# io-board-b-8.net
KiCad netlist of a schematic drawn in EAGLE
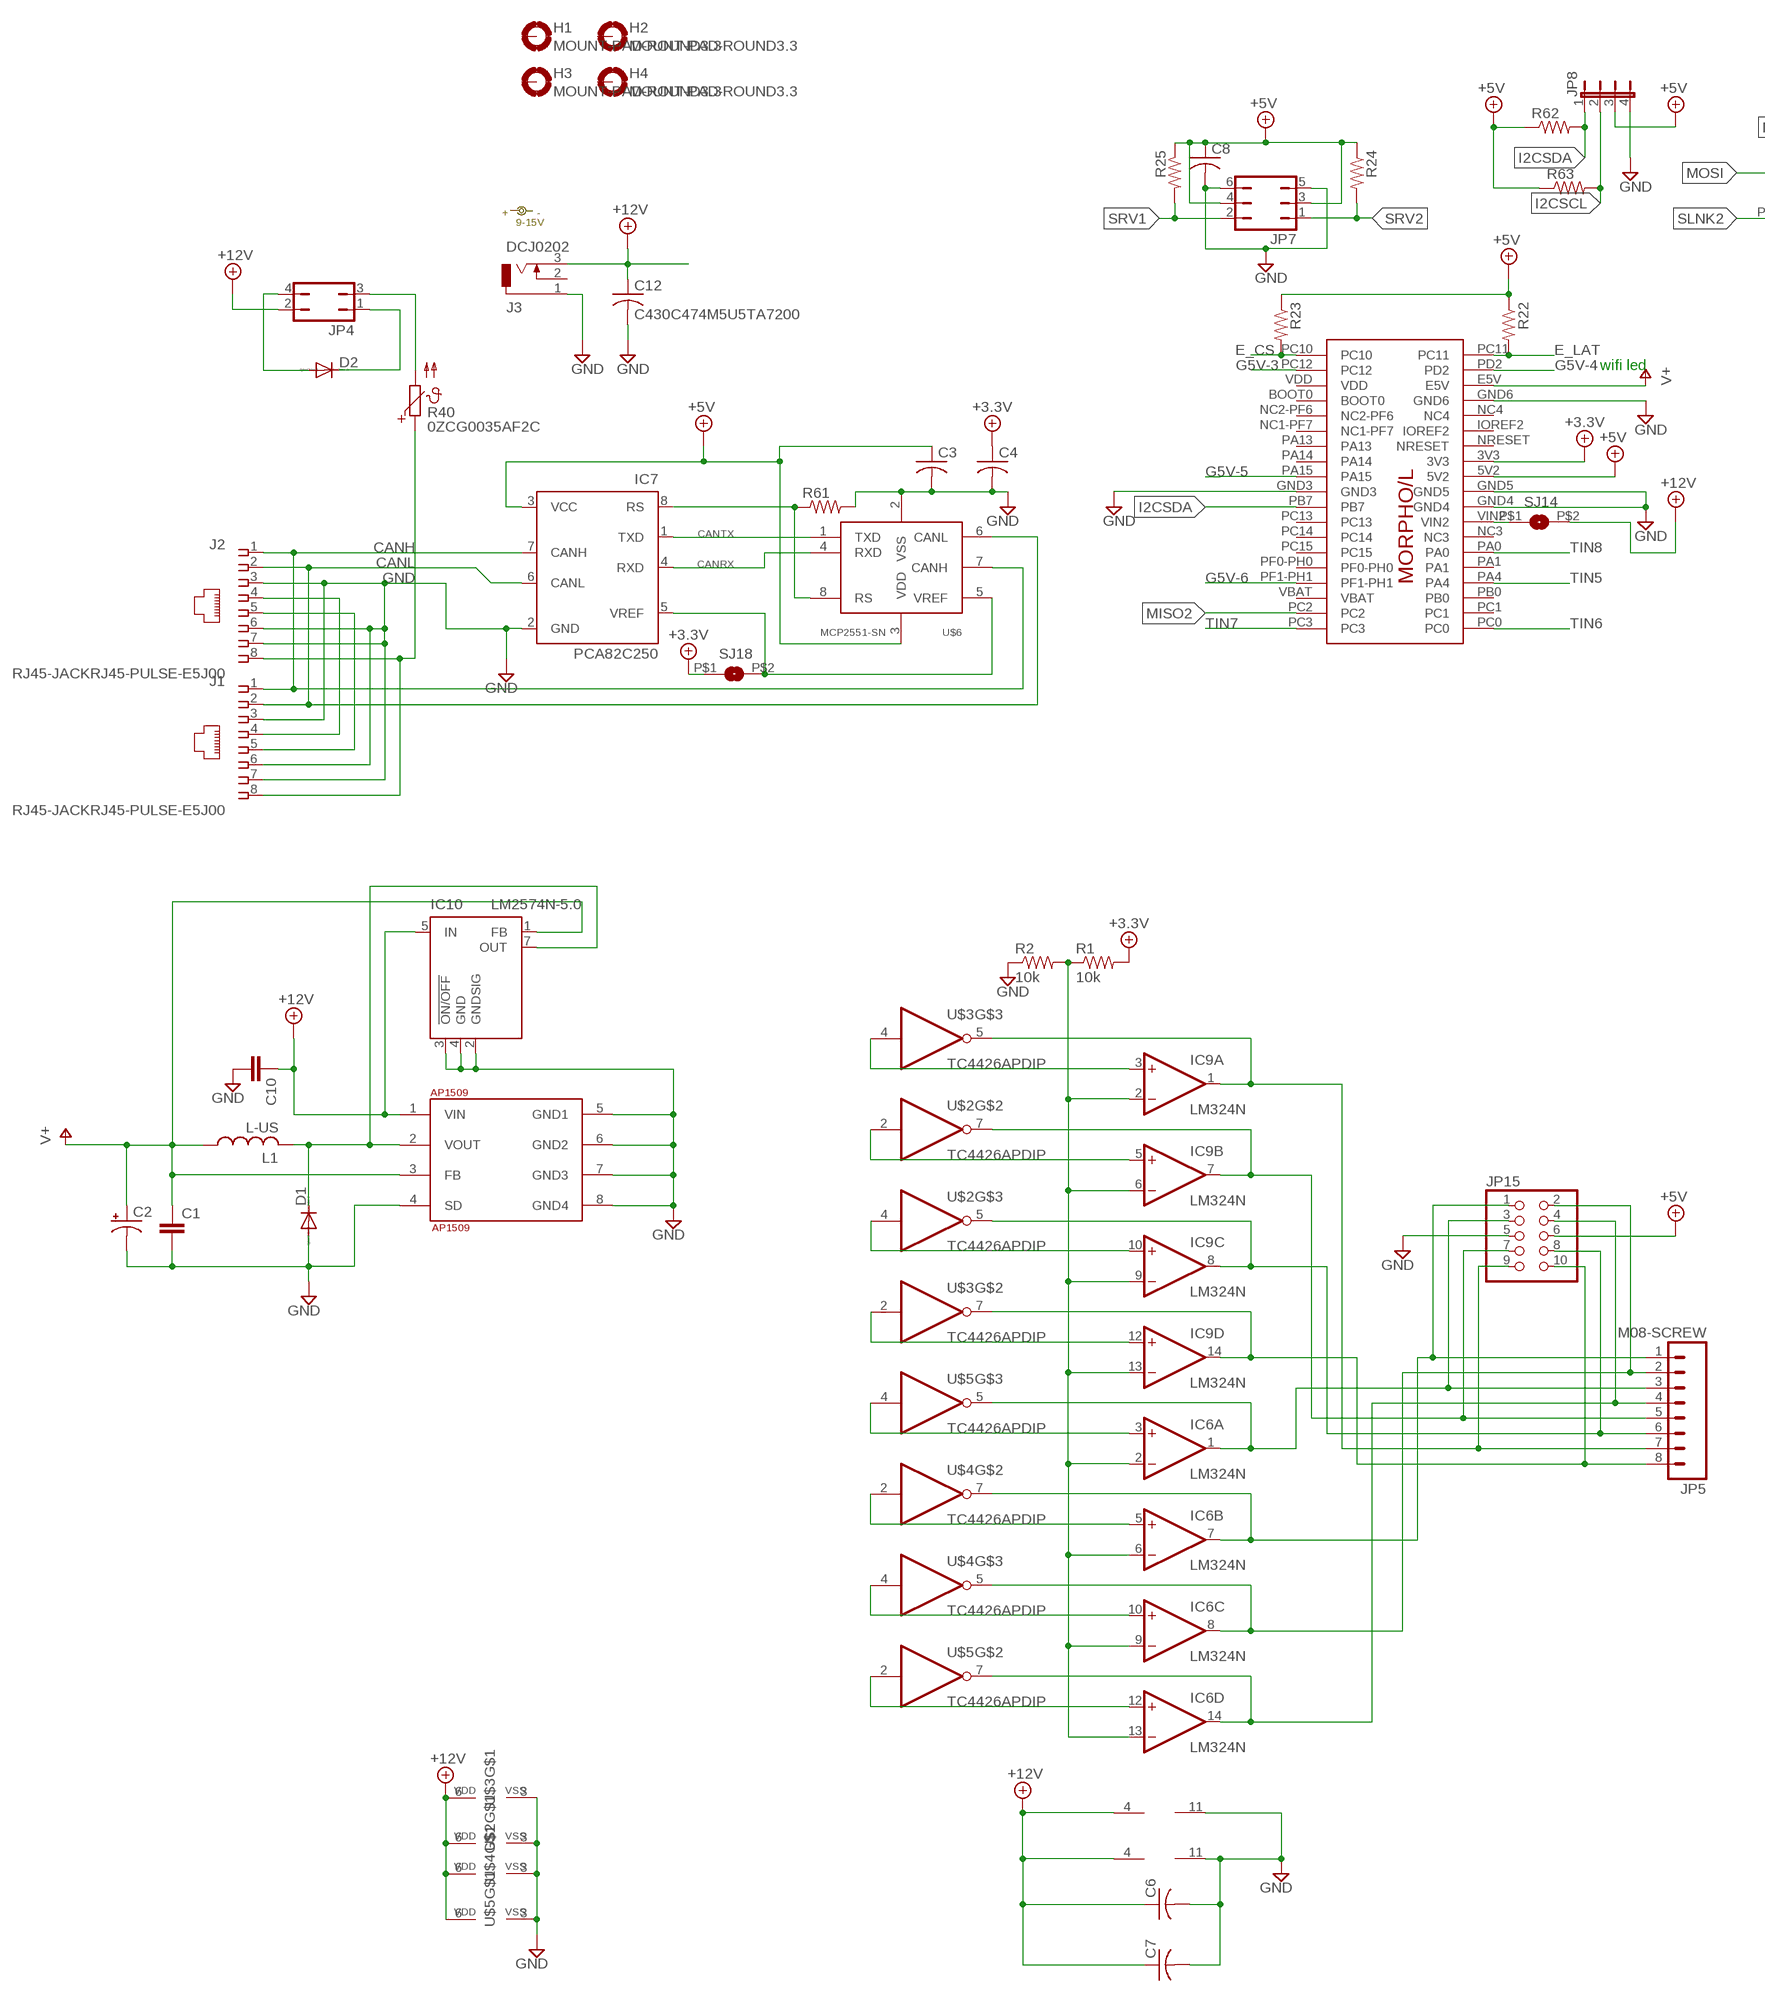
[diagram p0: schematic, sheet 1, part 1 of 2]
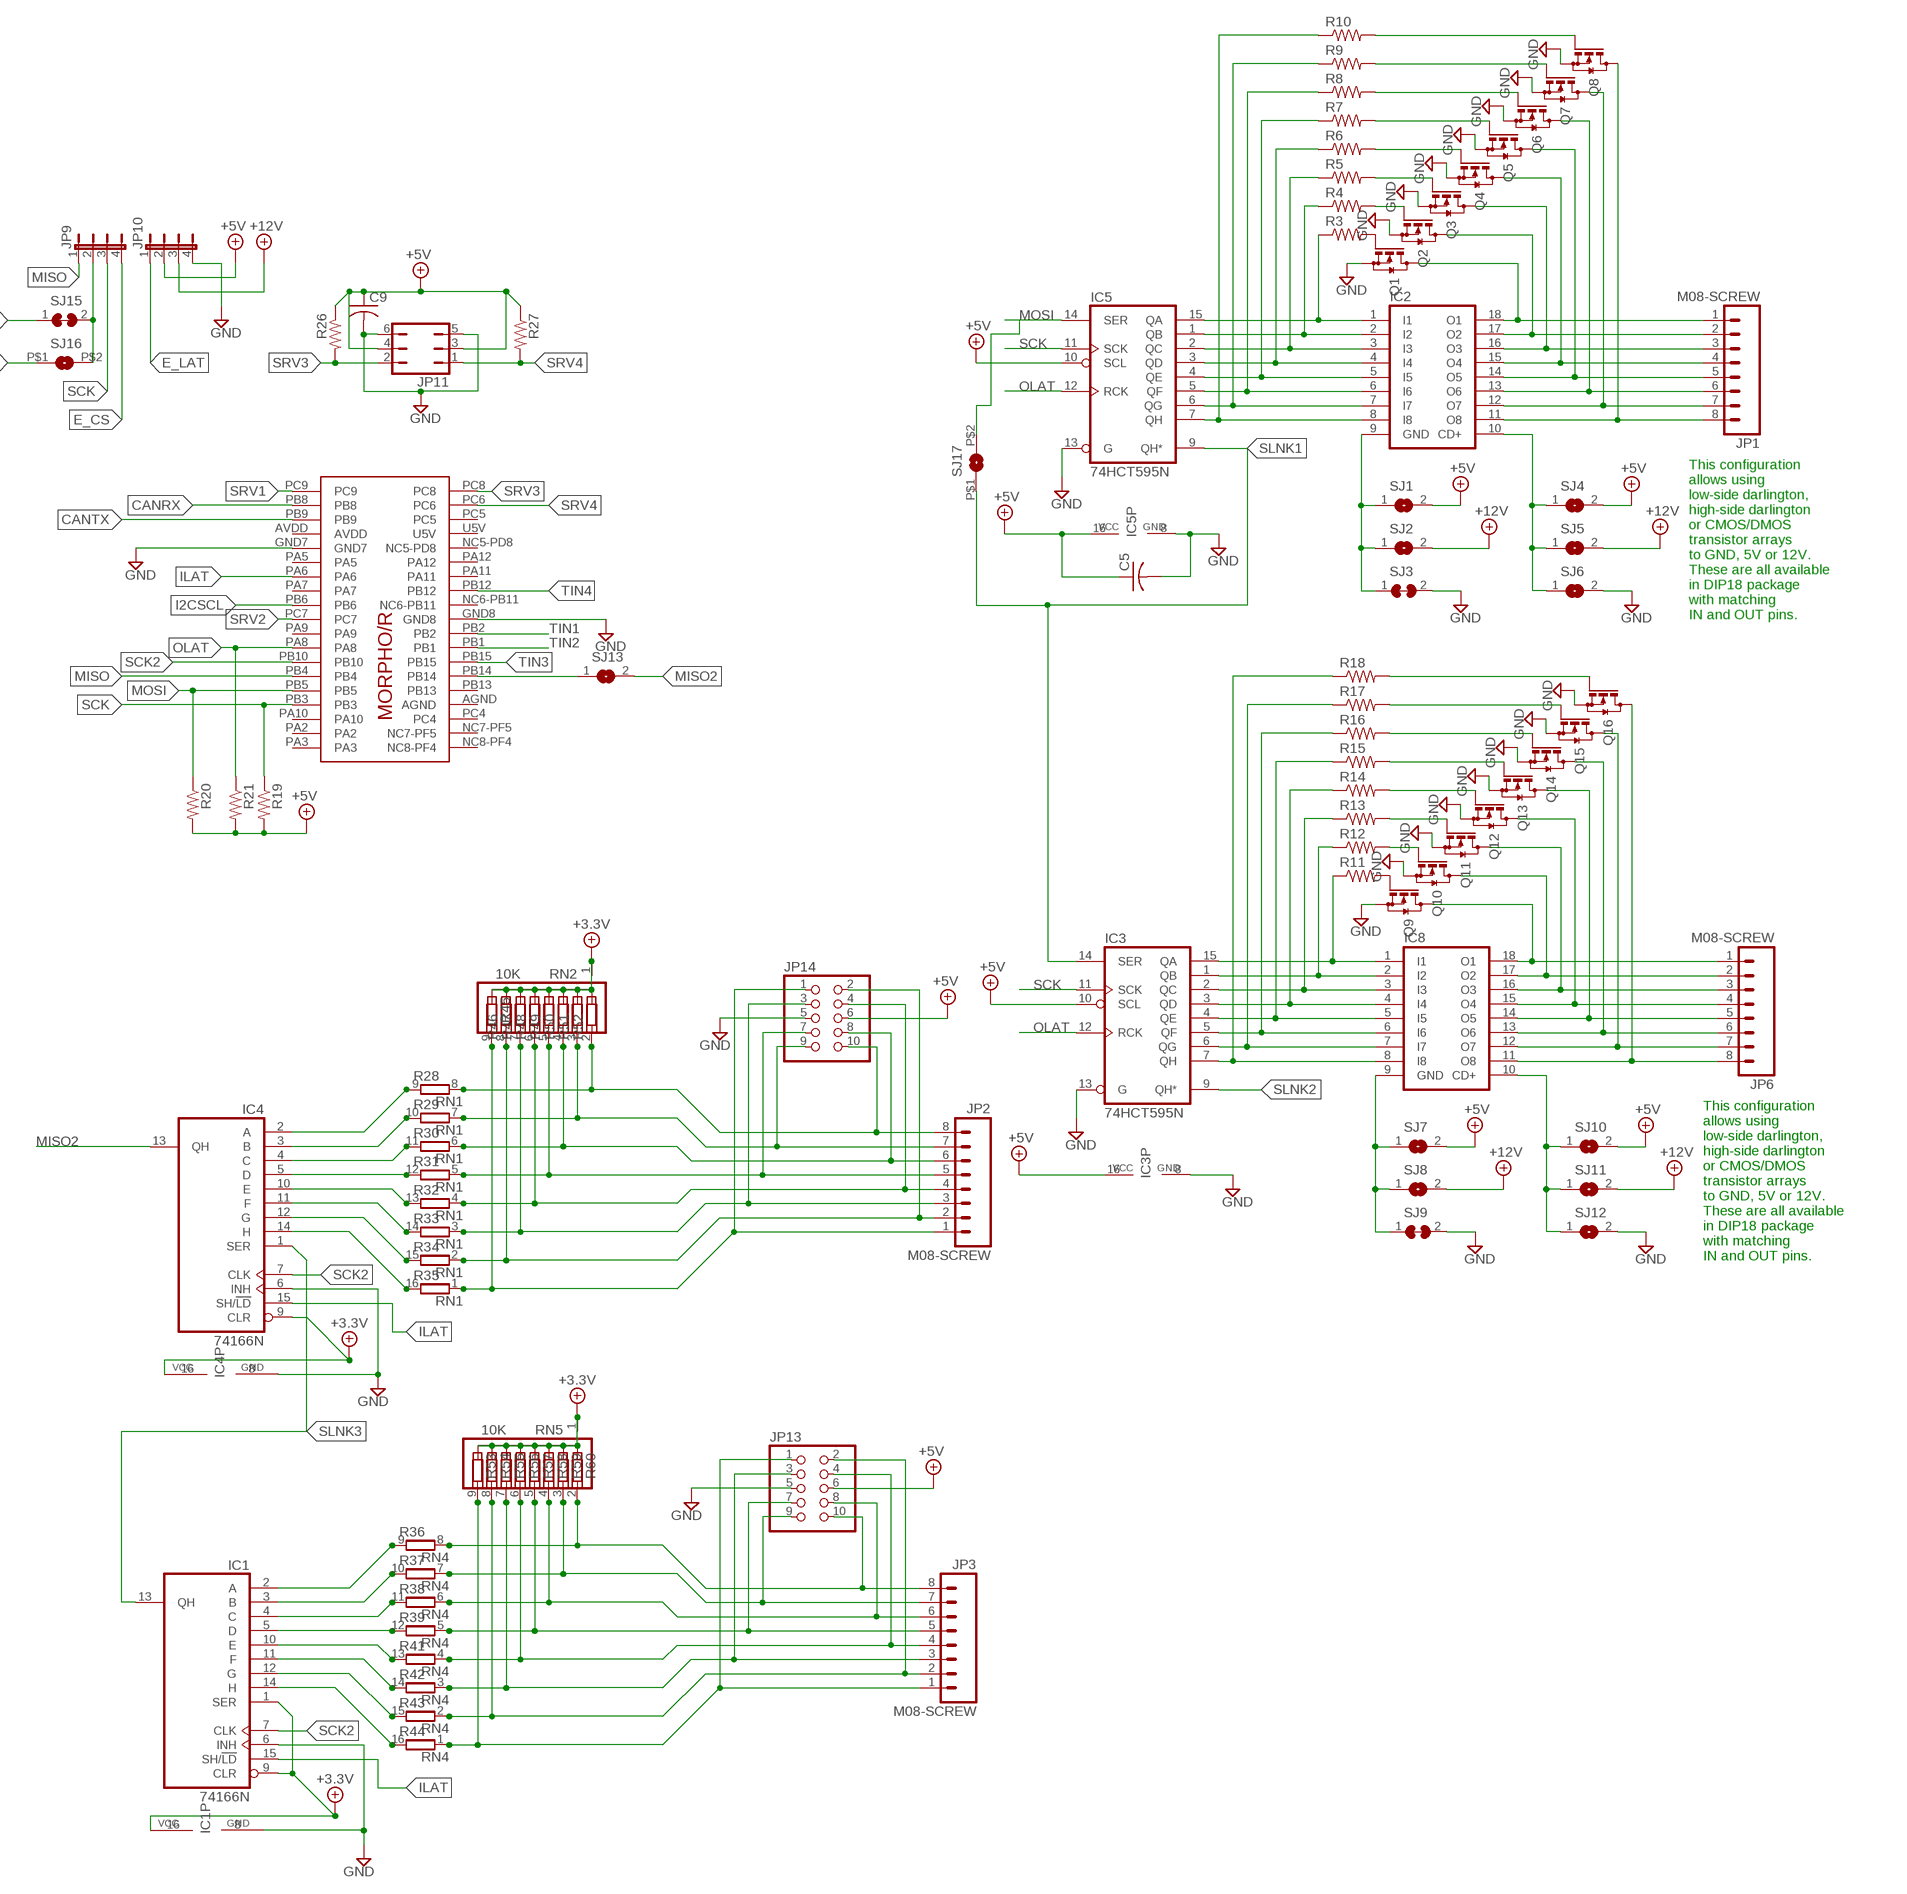
[diagram p1: schematic, sheet 1, part 2 of 2]

(export (version "E")
  (design (tool "Eeschema 10.0.6"))
  (components
    (comp (ref "+12V")
      (value "9-15V")
      (footprint "eagle-import:POWER_USAGE")
      (libsource (lib "eagle-import") (part "DOC-POWER_LABEL"))
    )
    (comp (ref "AP1509")
      (value "AP1509")
      (footprint "eagle-import:SO-08")
      (libsource (lib "eagle-import") (part "AP1509"))
    )
    (comp (ref "C1")
      (value "C-EUC1206")
      (footprint "eagle-import:C1206")
      (libsource (lib "eagle-import") (part "C-EUC1206"))
    )
    (comp (ref "C2")
      (value "CPOL-USE2.5-5")
      (footprint "eagle-import:E2,5-5")
      (libsource (lib "eagle-import") (part "CPOL-USE2.5-5"))
    )
    (comp (ref "C3")
      (value "C-USC0805")
      (footprint "eagle-import:C0805")
      (libsource (lib "eagle-import") (part "C-USC0805"))
    )
    (comp (ref "C4")
      (value "C-USC0805")
      (footprint "eagle-import:C0805")
      (libsource (lib "eagle-import") (part "C-USC0805"))
    )
    (comp (ref "C5")
      (value "C-USC0805")
      (footprint "eagle-import:C0805")
      (libsource (lib "eagle-import") (part "C-USC0805"))
    )
    (comp (ref "C6")
      (value "C-USC1206")
      (footprint "eagle-import:C1206")
      (libsource (lib "eagle-import") (part "C-USC1206"))
    )
    (comp (ref "C7")
      (value "C-USC1206")
      (footprint "eagle-import:C1206")
      (libsource (lib "eagle-import") (part "C-USC1206"))
    )
    (comp (ref "C8")
      (value "C-USC1206")
      (footprint "eagle-import:C1206")
      (libsource (lib "eagle-import") (part "C-USC1206"))
    )
    (comp (ref "C9")
      (value "C-USC1206")
      (footprint "eagle-import:C1206")
      (libsource (lib "eagle-import") (part "C-USC1206"))
    )
    (comp (ref "C10")
      (value "C-EUC1206")
      (footprint "eagle-import:C1206")
      (libsource (lib "eagle-import") (part "C-EUC1206"))
    )
    (comp (ref "C12")
      (value "C430C474M5U5TA7200")
      (footprint "eagle-import:C075-032X103")
      (libsource (lib "eagle-import") (part "C-US075-032X103"))
    )
    (comp (ref "D1")
      (value "DIODE-DO41-7.6")
      (footprint "eagle-import:DO41-7.6")
      (libsource (lib "eagle-import") (part "DIODE-DO41-7.6"))
    )
    (comp (ref "D2")
      (value "DIODE-DO41-7.6")
      (footprint "eagle-import:DO41-7.6")
      (libsource (lib "eagle-import") (part "DIODE-DO41-7.6"))
    )
    (comp (ref "H1")
      (value "MOUNT-PAD-ROUND3.3")
      (footprint "eagle-import:3,3-PAD")
      (libsource (lib "eagle-import") (part "MOUNT-PAD-ROUND3.3"))
    )
    (comp (ref "H2")
      (value "MOUNT-PAD-ROUND3.3")
      (footprint "eagle-import:3,3-PAD")
      (libsource (lib "eagle-import") (part "MOUNT-PAD-ROUND3.3"))
    )
    (comp (ref "H3")
      (value "MOUNT-PAD-ROUND3.3")
      (footprint "eagle-import:3,3-PAD")
      (libsource (lib "eagle-import") (part "MOUNT-PAD-ROUND3.3"))
    )
    (comp (ref "H4")
      (value "MOUNT-PAD-ROUND3.3")
      (footprint "eagle-import:3,3-PAD")
      (libsource (lib "eagle-import") (part "MOUNT-PAD-ROUND3.3"))
    )
    (comp (ref "IC1")
      (value "74166N")
      (footprint "eagle-import:DIL16")
      (libsource (lib "eagle-import") (part "74166N"))
    )
    (comp (ref "IC2")
      (value "ULN2803A")
      (footprint "eagle-import:DIL18-THIN")
      (libsource (lib "eagle-import") (part "ULN2803A"))
    )
    (comp (ref "IC3")
      (value "74HCT595N")
      (footprint "eagle-import:DIL16")
      (libsource (lib "eagle-import") (part "74595NHCT"))
    )
    (comp (ref "IC4")
      (value "74166N")
      (footprint "eagle-import:DIL16")
      (libsource (lib "eagle-import") (part "74166N"))
    )
    (comp (ref "IC5")
      (value "74HCT595N")
      (footprint "eagle-import:DIL16")
      (libsource (lib "eagle-import") (part "74595NHCT"))
    )
    (comp (ref "IC6")
      (value "LM324N")
      (footprint "eagle-import:DIL14")
      (libsource (lib "eagle-import") (part "LM324N"))
    )
    (comp (ref "IC7")
      (value "PCA82C250")
      (footprint "eagle-import:DIL08")
      (libsource (lib "eagle-import") (part "PCA82C250"))
    )
    (comp (ref "IC8")
      (value "ULN2803A")
      (footprint "eagle-import:DIL18-THIN")
      (libsource (lib "eagle-import") (part "ULN2803A"))
    )
    (comp (ref "IC9")
      (value "LM324N")
      (footprint "eagle-import:DIL14")
      (libsource (lib "eagle-import") (part "LM324N"))
    )
    (comp (ref "IC10")
      (value "LM2574N-5.0")
      (footprint "eagle-import:DIL08")
      (libsource (lib "eagle-import") (part "LM2574?-N5.0"))
    )
    (comp (ref "J1")
      (value "RJ45-JACKRJ45-PULSE-E5J00")
      (footprint "eagle-import:RJ45-PULSE-E5J88")
      (libsource (lib "eagle-import") (part "RJ45-JACKRJ45-PULSE-E5J00"))
    )
    (comp (ref "J2")
      (value "RJ45-JACKRJ45-PULSE-E5J00")
      (footprint "eagle-import:RJ45-PULSE-E5J88")
      (libsource (lib "eagle-import") (part "RJ45-JACKRJ45-PULSE-E5J00"))
    )
    (comp (ref "J3")
      (value "DCJ0202")
      (footprint "eagle-import:DCJ0202")
      (libsource (lib "eagle-import") (part "DCJ0202"))
    )
    (comp (ref "JP1")
      (value "M08-SCREW")
      (footprint "eagle-import:1X08_TERMINAL")
      (libsource (lib "eagle-import") (part "M08-SCREW"))
    )
    (comp (ref "JP2")
      (value "M08-SCREW")
      (footprint "eagle-import:1X08_TERMINAL")
      (libsource (lib "eagle-import") (part "M08-SCREW"))
    )
    (comp (ref "JP3")
      (value "M08-SCREW")
      (footprint "eagle-import:1X08_TERMINAL")
      (libsource (lib "eagle-import") (part "M08-SCREW"))
    )
    (comp (ref "JP4")
      (value "JP2Q")
      (footprint "eagle-import:JP2Q")
      (libsource (lib "eagle-import") (part "JP2Q"))
    )
    (comp (ref "JP5")
      (value "M08-SCREW")
      (footprint "eagle-import:1X08_TERMINAL")
      (libsource (lib "eagle-import") (part "M08-SCREW"))
    )
    (comp (ref "JP6")
      (value "M08-SCREW")
      (footprint "eagle-import:1X08_TERMINAL")
      (libsource (lib "eagle-import") (part "M08-SCREW"))
    )
    (comp (ref "JP7")
      (value "JP3Q")
      (footprint "eagle-import:JP3Q")
      (libsource (lib "eagle-import") (part "JP3Q"))
    )
    (comp (ref "JP8")
      (value "JP4-FLAT")
      (footprint "eagle-import:JP4F")
      (libsource (lib "eagle-import") (part "JP4-FLAT"))
    )
    (comp (ref "JP9")
      (value "JP4-FLAT")
      (footprint "eagle-import:JP4F")
      (libsource (lib "eagle-import") (part "JP4-FLAT"))
    )
    (comp (ref "JP10")
      (value "JP4-FLAT")
      (footprint "eagle-import:JP4F")
      (libsource (lib "eagle-import") (part "JP4-FLAT"))
    )
    (comp (ref "JP11")
      (value "JP3Q")
      (footprint "eagle-import:JP3Q")
      (libsource (lib "eagle-import") (part "JP3Q"))
    )
    (comp (ref "JP13")
      (value "PINHD-2X5CN")
      (footprint "eagle-import:CON10M")
      (libsource (lib "eagle-import") (part "PINHD-2X5CN"))
    )
    (comp (ref "JP14")
      (value "PINHD-2X5CN")
      (footprint "eagle-import:CON10M")
      (libsource (lib "eagle-import") (part "PINHD-2X5CN"))
    )
    (comp (ref "JP15")
      (value "PINHD-2X5CN")
      (footprint "eagle-import:CON10M")
      (libsource (lib "eagle-import") (part "PINHD-2X5CN"))
    )
    (comp (ref "L1")
      (value "L-US")
      (footprint "eagle-import:L5-8,5")
      (libsource (lib "eagle-import") (part "L-US"))
    )
    (comp (ref "Q1")
      (value "BSS123")
      (footprint "eagle-import:SOT23")
      (libsource (lib "eagle-import") (part "BSS123"))
    )
    (comp (ref "Q2")
      (value "BSS123")
      (footprint "eagle-import:SOT23")
      (libsource (lib "eagle-import") (part "BSS123"))
    )
    (comp (ref "Q3")
      (value "BSS123")
      (footprint "eagle-import:SOT23")
      (libsource (lib "eagle-import") (part "BSS123"))
    )
    (comp (ref "Q4")
      (value "BSS123")
      (footprint "eagle-import:SOT23")
      (libsource (lib "eagle-import") (part "BSS123"))
    )
    (comp (ref "Q5")
      (value "BSS123")
      (footprint "eagle-import:SOT23")
      (libsource (lib "eagle-import") (part "BSS123"))
    )
    (comp (ref "Q6")
      (value "BSS123")
      (footprint "eagle-import:SOT23")
      (libsource (lib "eagle-import") (part "BSS123"))
    )
    (comp (ref "Q7")
      (value "BSS123")
      (footprint "eagle-import:SOT23")
      (libsource (lib "eagle-import") (part "BSS123"))
    )
    (comp (ref "Q8")
      (value "BSS123")
      (footprint "eagle-import:SOT23")
      (libsource (lib "eagle-import") (part "BSS123"))
    )
    (comp (ref "Q9")
      (value "BSS123")
      (footprint "eagle-import:SOT23")
      (libsource (lib "eagle-import") (part "BSS123"))
    )
    (comp (ref "Q10")
      (value "BSS123")
      (footprint "eagle-import:SOT23")
      (libsource (lib "eagle-import") (part "BSS123"))
    )
    (comp (ref "Q11")
      (value "BSS123")
      (footprint "eagle-import:SOT23")
      (libsource (lib "eagle-import") (part "BSS123"))
    )
    (comp (ref "Q12")
      (value "BSS123")
      (footprint "eagle-import:SOT23")
      (libsource (lib "eagle-import") (part "BSS123"))
    )
    (comp (ref "Q13")
      (value "BSS123")
      (footprint "eagle-import:SOT23")
      (libsource (lib "eagle-import") (part "BSS123"))
    )
    (comp (ref "Q14")
      (value "BSS123")
      (footprint "eagle-import:SOT23")
      (libsource (lib "eagle-import") (part "BSS123"))
    )
    (comp (ref "Q15")
      (value "BSS123")
      (footprint "eagle-import:SOT23")
      (libsource (lib "eagle-import") (part "BSS123"))
    )
    (comp (ref "Q16")
      (value "BSS123")
      (footprint "eagle-import:SOT23")
      (libsource (lib "eagle-import") (part "BSS123"))
    )
    (comp (ref "R1")
      (value "10k")
      (footprint "eagle-import:R0805")
      (libsource (lib "eagle-import") (part "R-US_R0805"))
    )
    (comp (ref "R2")
      (value "10k")
      (footprint "eagle-import:R0805")
      (libsource (lib "eagle-import") (part "R-US_R0805"))
    )
    (comp (ref "R3")
      (value "R-US_R0603")
      (footprint "eagle-import:R0603")
      (libsource (lib "eagle-import") (part "R-US_R0603"))
    )
    (comp (ref "R4")
      (value "R-US_R0603")
      (footprint "eagle-import:R0603")
      (libsource (lib "eagle-import") (part "R-US_R0603"))
    )
    (comp (ref "R5")
      (value "R-US_R0603")
      (footprint "eagle-import:R0603")
      (libsource (lib "eagle-import") (part "R-US_R0603"))
    )
    (comp (ref "R6")
      (value "R-US_R0603")
      (footprint "eagle-import:R0603")
      (libsource (lib "eagle-import") (part "R-US_R0603"))
    )
    (comp (ref "R7")
      (value "R-US_R0603")
      (footprint "eagle-import:R0603")
      (libsource (lib "eagle-import") (part "R-US_R0603"))
    )
    (comp (ref "R8")
      (value "R-US_R0603")
      (footprint "eagle-import:R0603")
      (libsource (lib "eagle-import") (part "R-US_R0603"))
    )
    (comp (ref "R9")
      (value "R-US_R0603")
      (footprint "eagle-import:R0603")
      (libsource (lib "eagle-import") (part "R-US_R0603"))
    )
    (comp (ref "R10")
      (value "R-US_R0603")
      (footprint "eagle-import:R0603")
      (libsource (lib "eagle-import") (part "R-US_R0603"))
    )
    (comp (ref "R11")
      (value "R-US_R0603")
      (footprint "eagle-import:R0603")
      (libsource (lib "eagle-import") (part "R-US_R0603"))
    )
    (comp (ref "R12")
      (value "R-US_R0603")
      (footprint "eagle-import:R0603")
      (libsource (lib "eagle-import") (part "R-US_R0603"))
    )
    (comp (ref "R13")
      (value "R-US_R0603")
      (footprint "eagle-import:R0603")
      (libsource (lib "eagle-import") (part "R-US_R0603"))
    )
    (comp (ref "R14")
      (value "R-US_R0603")
      (footprint "eagle-import:R0603")
      (libsource (lib "eagle-import") (part "R-US_R0603"))
    )
    (comp (ref "R15")
      (value "R-US_R0603")
      (footprint "eagle-import:R0603")
      (libsource (lib "eagle-import") (part "R-US_R0603"))
    )
    (comp (ref "R16")
      (value "R-US_R0603")
      (footprint "eagle-import:R0603")
      (libsource (lib "eagle-import") (part "R-US_R0603"))
    )
    (comp (ref "R17")
      (value "R-US_R0603")
      (footprint "eagle-import:R0603")
      (libsource (lib "eagle-import") (part "R-US_R0603"))
    )
    (comp (ref "R18")
      (value "R-US_R0603")
      (footprint "eagle-import:R0603")
      (libsource (lib "eagle-import") (part "R-US_R0603"))
    )
    (comp (ref "R19")
      (value "R-US_R0805")
      (footprint "eagle-import:R0805")
      (libsource (lib "eagle-import") (part "rcl_334_R-US_R0805"))
    )
    (comp (ref "R20")
      (value "R-US_R0805")
      (footprint "eagle-import:R0805")
      (libsource (lib "eagle-import") (part "rcl_334_R-US_R0805"))
    )
    (comp (ref "R21")
      (value "R-US_R0805")
      (footprint "eagle-import:R0805")
      (libsource (lib "eagle-import") (part "rcl_334_R-US_R0805"))
    )
    (comp (ref "R22")
      (value "R-US_R0805")
      (footprint "eagle-import:R0805")
      (libsource (lib "eagle-import") (part "rcl_334_R-US_R0805"))
    )
    (comp (ref "R23")
      (value "R-US_R0805")
      (footprint "eagle-import:R0805")
      (libsource (lib "eagle-import") (part "rcl_334_R-US_R0805"))
    )
    (comp (ref "R24")
      (value "R-US_R0805")
      (footprint "eagle-import:R0805")
      (libsource (lib "eagle-import") (part "rcl_334_R-US_R0805"))
    )
    (comp (ref "R25")
      (value "R-US_R0805")
      (footprint "eagle-import:R0805")
      (libsource (lib "eagle-import") (part "rcl_334_R-US_R0805"))
    )
    (comp (ref "R26")
      (value "R-US_R0805")
      (footprint "eagle-import:R0805")
      (libsource (lib "eagle-import") (part "rcl_334_R-US_R0805"))
    )
    (comp (ref "R27")
      (value "R-US_R0805")
      (footprint "eagle-import:R0805")
      (libsource (lib "eagle-import") (part "rcl_334_R-US_R0805"))
    )
    (comp (ref "R28")
      (value "R-EU_R0603")
      (footprint "eagle-import:R0603")
      (libsource (lib "eagle-import") (part "R-EU_R0603"))
    )
    (comp (ref "R29")
      (value "R-EU_R0603")
      (footprint "eagle-import:R0603")
      (libsource (lib "eagle-import") (part "R-EU_R0603"))
    )
    (comp (ref "R30")
      (value "R-EU_R0603")
      (footprint "eagle-import:R0603")
      (libsource (lib "eagle-import") (part "R-EU_R0603"))
    )
    (comp (ref "R31")
      (value "R-EU_R0603")
      (footprint "eagle-import:R0603")
      (libsource (lib "eagle-import") (part "R-EU_R0603"))
    )
    (comp (ref "R32")
      (value "R-EU_R0603")
      (footprint "eagle-import:R0603")
      (libsource (lib "eagle-import") (part "R-EU_R0603"))
    )
    (comp (ref "R33")
      (value "R-EU_R0603")
      (footprint "eagle-import:R0603")
      (libsource (lib "eagle-import") (part "R-EU_R0603"))
    )
    (comp (ref "R34")
      (value "R-EU_R0603")
      (footprint "eagle-import:R0603")
      (libsource (lib "eagle-import") (part "R-EU_R0603"))
    )
    (comp (ref "R35")
      (value "R-EU_R0603")
      (footprint "eagle-import:R0603")
      (libsource (lib "eagle-import") (part "R-EU_R0603"))
    )
    (comp (ref "R36")
      (value "R-EU_R0603")
      (footprint "eagle-import:R0603")
      (libsource (lib "eagle-import") (part "R-EU_R0603"))
    )
    (comp (ref "R37")
      (value "R-EU_R0603")
      (footprint "eagle-import:R0603")
      (libsource (lib "eagle-import") (part "R-EU_R0603"))
    )
    (comp (ref "R38")
      (value "R-EU_R0603")
      (footprint "eagle-import:R0603")
      (libsource (lib "eagle-import") (part "R-EU_R0603"))
    )
    (comp (ref "R39")
      (value "R-EU_R0603")
      (footprint "eagle-import:R0603")
      (libsource (lib "eagle-import") (part "R-EU_R0603"))
    )
    (comp (ref "R40")
      (value "0ZCG0035AF2C")
      (footprint "eagle-import:PTC1812")
      (libsource (lib "eagle-import") (part "PTC_1812"))
    )
    (comp (ref "R41")
      (value "R-EU_R0603")
      (footprint "eagle-import:R0603")
      (libsource (lib "eagle-import") (part "R-EU_R0603"))
    )
    (comp (ref "R42")
      (value "R-EU_R0603")
      (footprint "eagle-import:R0603")
      (libsource (lib "eagle-import") (part "R-EU_R0603"))
    )
    (comp (ref "R43")
      (value "R-EU_R0603")
      (footprint "eagle-import:R0603")
      (libsource (lib "eagle-import") (part "R-EU_R0603"))
    )
    (comp (ref "R44")
      (value "R-EU_R0603")
      (footprint "eagle-import:R0603")
      (libsource (lib "eagle-import") (part "R-EU_R0603"))
    )
    (comp (ref "R45")
      (value "R-EU_R0603")
      (footprint "eagle-import:R0603")
      (libsource (lib "eagle-import") (part "R-EU_R0603"))
    )
    (comp (ref "R46")
      (value "R-EU_R0603")
      (footprint "eagle-import:R0603")
      (libsource (lib "eagle-import") (part "R-EU_R0603"))
    )
    (comp (ref "R47")
      (value "R-EU_R0603")
      (footprint "eagle-import:R0603")
      (libsource (lib "eagle-import") (part "R-EU_R0603"))
    )
    (comp (ref "R48")
      (value "R-EU_R0603")
      (footprint "eagle-import:R0603")
      (libsource (lib "eagle-import") (part "R-EU_R0603"))
    )
    (comp (ref "R49")
      (value "R-EU_R0603")
      (footprint "eagle-import:R0603")
      (libsource (lib "eagle-import") (part "R-EU_R0603"))
    )
    (comp (ref "R50")
      (value "R-EU_R0603")
      (footprint "eagle-import:R0603")
      (libsource (lib "eagle-import") (part "R-EU_R0603"))
    )
    (comp (ref "R51")
      (value "R-EU_R0603")
      (footprint "eagle-import:R0603")
      (libsource (lib "eagle-import") (part "R-EU_R0603"))
    )
    (comp (ref "R52")
      (value "R-EU_R0603")
      (footprint "eagle-import:R0603")
      (libsource (lib "eagle-import") (part "R-EU_R0603"))
    )
    (comp (ref "R53")
      (value "R-EU_R0603")
      (footprint "eagle-import:R0603")
      (libsource (lib "eagle-import") (part "R-EU_R0603"))
    )
    (comp (ref "R54")
      (value "R-EU_R0603")
      (footprint "eagle-import:R0603")
      (libsource (lib "eagle-import") (part "R-EU_R0603"))
    )
    (comp (ref "R55")
      (value "R-EU_R0603")
      (footprint "eagle-import:R0603")
      (libsource (lib "eagle-import") (part "R-EU_R0603"))
    )
    (comp (ref "R56")
      (value "R-EU_R0603")
      (footprint "eagle-import:R0603")
      (libsource (lib "eagle-import") (part "R-EU_R0603"))
    )
    (comp (ref "R57")
      (value "R-EU_R0603")
      (footprint "eagle-import:R0603")
      (libsource (lib "eagle-import") (part "R-EU_R0603"))
    )
    (comp (ref "R58")
      (value "R-EU_R0603")
      (footprint "eagle-import:R0603")
      (libsource (lib "eagle-import") (part "R-EU_R0603"))
    )
    (comp (ref "R59")
      (value "R-EU_R0603")
      (footprint "eagle-import:R0603")
      (libsource (lib "eagle-import") (part "R-EU_R0603"))
    )
    (comp (ref "R60")
      (value "R-EU_R0603")
      (footprint "eagle-import:R0603")
      (libsource (lib "eagle-import") (part "R-EU_R0603"))
    )
    (comp (ref "R61")
      (value "R-US_R0805")
      (footprint "eagle-import:R0805")
      (libsource (lib "eagle-import") (part "rcl_334_R-US_R0805"))
    )
    (comp (ref "R62")
      (value "R-US_R0805")
      (footprint "eagle-import:R0805")
      (libsource (lib "eagle-import") (part "rcl_334_R-US_R0805"))
    )
    (comp (ref "R63")
      (value "R-US_R0805")
      (footprint "eagle-import:R0805")
      (libsource (lib "eagle-import") (part "rcl_334_R-US_R0805"))
    )
    (comp (ref "RN1")
      (value "8R-P")
      (footprint "eagle-import:DIL16")
      (libsource (lib "eagle-import") (part "8R-P"))
    )
    (comp (ref "RN2")
      (value "10K")
      (footprint "eagle-import:SIL9")
      (libsource (lib "eagle-import") (part "G08R"))
    )
    (comp (ref "RN4")
      (value "8R-P")
      (footprint "eagle-import:DIL16")
      (libsource (lib "eagle-import") (part "8R-P"))
    )
    (comp (ref "RN5")
      (value "10K")
      (footprint "eagle-import:SIL9")
      (libsource (lib "eagle-import") (part "G08R"))
    )
    (comp (ref "SJ1")
      (value "SJ")
      (footprint "eagle-import:SJ-RND")
      (libsource (lib "eagle-import") (part "SJ"))
    )
    (comp (ref "SJ2")
      (value "SJ")
      (footprint "eagle-import:SJ-RND")
      (libsource (lib "eagle-import") (part "SJ"))
    )
    (comp (ref "SJ3")
      (value "SJ-C")
      (footprint "eagle-import:SJW-C")
      (libsource (lib "eagle-import") (part "SJ-C"))
    )
    (comp (ref "SJ4")
      (value "SJ")
      (footprint "eagle-import:SJ-RND")
      (libsource (lib "eagle-import") (part "SJ"))
    )
    (comp (ref "SJ5")
      (value "SJ")
      (footprint "eagle-import:SJ-RND")
      (libsource (lib "eagle-import") (part "SJ"))
    )
    (comp (ref "SJ6")
      (value "SJ")
      (footprint "eagle-import:SJ-RND")
      (libsource (lib "eagle-import") (part "SJ"))
    )
    (comp (ref "SJ7")
      (value "SJ")
      (footprint "eagle-import:SJ-RND")
      (libsource (lib "eagle-import") (part "SJ"))
    )
    (comp (ref "SJ8")
      (value "SJ")
      (footprint "eagle-import:SJ-RND")
      (libsource (lib "eagle-import") (part "SJ"))
    )
    (comp (ref "SJ9")
      (value "SJ-C")
      (footprint "eagle-import:SJW-C")
      (libsource (lib "eagle-import") (part "SJ-C"))
    )
    (comp (ref "SJ10")
      (value "SJ")
      (footprint "eagle-import:SJ-RND")
      (libsource (lib "eagle-import") (part "SJ"))
    )
    (comp (ref "SJ11")
      (value "SJ")
      (footprint "eagle-import:SJ-RND")
      (libsource (lib "eagle-import") (part "SJ"))
    )
    (comp (ref "SJ12")
      (value "SJ")
      (footprint "eagle-import:SJ-RND")
      (libsource (lib "eagle-import") (part "SJ"))
    )
    (comp (ref "SJ13")
      (value "SJ")
      (footprint "eagle-import:SJ-RND")
      (libsource (lib "eagle-import") (part "SJ"))
    )
    (comp (ref "SJ14")
      (value "SJRND2")
      (footprint "eagle-import:SJ_RND2")
      (libsource (lib "eagle-import") (part "SJRND2"))
    )
    (comp (ref "SJ15")
      (value "SJ-C")
      (footprint "eagle-import:SJW-C")
      (libsource (lib "eagle-import") (part "SJ-C"))
    )
    (comp (ref "SJ16")
      (value "SJRND2")
      (footprint "eagle-import:SJ_RND2")
      (libsource (lib "eagle-import") (part "SJRND2"))
    )
    (comp (ref "SJ17")
      (value "SJRND2")
      (footprint "eagle-import:SJ_RND2")
      (libsource (lib "eagle-import") (part "SJRND2"))
    )
    (comp (ref "SJ18")
      (value "SJRND2")
      (footprint "eagle-import:SJ_RND2")
      (libsource (lib "eagle-import") (part "SJRND2"))
    )
    (comp (ref "U$1")
      (value "NUCLEO_64_GENERIC")
      (footprint "eagle-import:NUCLEO_BRD_BASE64")
      (libsource (lib "eagle-import") (part "NUCLEO_64_GENERIC"))
    )
    (comp (ref "U$2")
      (value "TC4426APDIP")
      (footprint "eagle-import:DIL08-LONG")
      (libsource (lib "eagle-import") (part "TC4426APDIP"))
    )
    (comp (ref "U$3")
      (value "TC4426APDIP")
      (footprint "eagle-import:DIL08-LONG")
      (libsource (lib "eagle-import") (part "TC4426APDIP"))
    )
    (comp (ref "U$4")
      (value "TC4426APDIP")
      (footprint "eagle-import:DIL08-LONG")
      (libsource (lib "eagle-import") (part "TC4426APDIP"))
    )
    (comp (ref "U$5")
      (value "TC4426APDIP")
      (footprint "eagle-import:DIL08-LONG")
      (libsource (lib "eagle-import") (part "TC4426APDIP"))
    )
    (comp (ref "U$6")
      (value "MCP2551-SN")
      (footprint "eagle-import:SO-08")
      (libsource (lib "eagle-import") (part "MCP2551-SN"))
    )
  )
  (nets
    (net (code "1") (name "+3.3V") (class "Default")
      (node (ref "C4") (pin "1") (pinfunction "1_1") (pintype "passive"))
      (node (ref "IC1") (pin "1") (pinfunction "SER_1") (pintype "input"))
      (node (ref "IC1") (pin "16") (pinfunction "VCC_16") (pintype "power_in"))
      (node (ref "IC1") (pin "9") (pinfunction "CLR_9") (pintype "input"))
      (node (ref "IC4") (pin "16") (pinfunction "VCC_16") (pintype "power_in"))
      (node (ref "IC4") (pin "9") (pinfunction "CLR_9") (pintype "input"))
      (node (ref "R1") (pin "2") (pinfunction "2_2") (pintype "passive"))
      (node (ref "R45") (pin "1") (pinfunction "1_1") (pintype "passive"))
      (node (ref "R46") (pin "2") (pinfunction "2_2") (pintype "passive"))
      (node (ref "R47") (pin "2") (pinfunction "2_2") (pintype "passive"))
      (node (ref "R48") (pin "2") (pinfunction "2_2") (pintype "passive"))
      (node (ref "R49") (pin "2") (pinfunction "2_2") (pintype "passive"))
      (node (ref "R50") (pin "2") (pinfunction "2_2") (pintype "passive"))
      (node (ref "R51") (pin "2") (pinfunction "2_2") (pintype "passive"))
      (node (ref "R52") (pin "2") (pinfunction "2_2") (pintype "passive"))
      (node (ref "R53") (pin "1") (pinfunction "1_1") (pintype "passive"))
      (node (ref "R54") (pin "1") (pinfunction "1_1") (pintype "passive"))
      (node (ref "R55") (pin "1") (pinfunction "1_1") (pintype "passive"))
      (node (ref "R56") (pin "1") (pinfunction "1_1") (pintype "passive"))
      (node (ref "R57") (pin "1") (pinfunction "1_1") (pintype "passive"))
      (node (ref "R58") (pin "1") (pinfunction "1_1") (pintype "passive"))
      (node (ref "R59") (pin "1") (pinfunction "1_1") (pintype "passive"))
      (node (ref "R60") (pin "1") (pinfunction "1_1") (pintype "passive"))
      (node (ref "RN2") (pin "1") (pinfunction "1_1") (pintype "passive"))
      (node (ref "RN5") (pin "1") (pinfunction "1_1") (pintype "passive"))
      (node (ref "SJ18") (pin "P$1") (pinfunction "1_P$1") (pintype "passive"))
      (node (ref "U$1") (pin "3V3") (pinfunction "3V3_3V3") (pintype "power_in"))
    )
    (net (code "2") (name "+5V") (class "Default")
      (node (ref "C3") (pin "1") (pinfunction "1_1") (pintype "passive"))
      (node (ref "C5") (pin "1") (pinfunction "1_1") (pintype "passive"))
      (node (ref "C8") (pin "1") (pinfunction "1_1") (pintype "passive"))
      (node (ref "C9") (pin "1") (pinfunction "1_1") (pintype "passive"))
      (node (ref "IC3") (pin "10") (pinfunction "SCL_10") (pintype "input"))
      (node (ref "IC3") (pin "16") (pinfunction "VCC_16") (pintype "power_in"))
      (node (ref "IC5") (pin "10") (pinfunction "SCL_10") (pintype "input"))
      (node (ref "IC5") (pin "16") (pinfunction "VCC_16") (pintype "power_in"))
      (node (ref "IC7") (pin "3") (pinfunction "VCC_3") (pintype "power_in"))
      (node (ref "JP10") (pin "2") (pinfunction "2_2") (pintype "passive"))
      (node (ref "JP11") (pin "3") (pinfunction "3_3") (pintype "passive"))
      (node (ref "JP11") (pin "4") (pinfunction "4_4") (pintype "passive"))
      (node (ref "JP13") (pin "6") (pinfunction "6_6") (pintype "passive"))
      (node (ref "JP14") (pin "6") (pinfunction "6_6") (pintype "passive"))
      (node (ref "JP15") (pin "6") (pinfunction "6_6") (pintype "passive"))
      (node (ref "JP7") (pin "3") (pinfunction "3_3") (pintype "passive"))
      (node (ref "JP7") (pin "4") (pinfunction "4_4") (pintype "passive"))
      (node (ref "JP8") (pin "3") (pinfunction "3_3") (pintype "passive"))
      (node (ref "R19") (pin "2") (pinfunction "2_2") (pintype "passive"))
      (node (ref "R20") (pin "2") (pinfunction "2_2") (pintype "passive"))
      (node (ref "R21") (pin "2") (pinfunction "2_2") (pintype "passive"))
      (node (ref "R22") (pin "1") (pinfunction "1_1") (pintype "passive"))
      (node (ref "R23") (pin "1") (pinfunction "1_1") (pintype "passive"))
      (node (ref "R24") (pin "1") (pinfunction "1_1") (pintype "passive"))
      (node (ref "R25") (pin "1") (pinfunction "1_1") (pintype "passive"))
      (node (ref "R26") (pin "1") (pinfunction "1_1") (pintype "passive"))
      (node (ref "R27") (pin "1") (pinfunction "1_1") (pintype "passive"))
      (node (ref "R62") (pin "1") (pinfunction "1_1") (pintype "passive"))
      (node (ref "R63") (pin "1") (pinfunction "1_1") (pintype "passive"))
      (node (ref "SJ1") (pin "2") (pinfunction "2_2") (pintype "passive"))
      (node (ref "SJ10") (pin "2") (pinfunction "2_2") (pintype "passive"))
      (node (ref "SJ4") (pin "2") (pinfunction "2_2") (pintype "passive"))
      (node (ref "SJ7") (pin "2") (pinfunction "2_2") (pintype "passive"))
      (node (ref "U$1") (pin "5V2") (pinfunction "5V2_5V2") (pintype "power_in"))
      (node (ref "U$6") (pin "3") (pinfunction "VDD_3") (pintype "power_in"))
    )
    (net (code "3") (name "+12V") (class "Default")
      (node (ref "AP1509") (pin "1") (pinfunction "VIN_1") (pintype "bidirectional"))
      (node (ref "C10") (pin "1") (pinfunction "1_1") (pintype "passive"))
      (node (ref "C12") (pin "1") (pinfunction "1_1") (pintype "passive"))
      (node (ref "C6") (pin "1") (pinfunction "1_1") (pintype "passive"))
      (node (ref "C7") (pin "1") (pinfunction "1_1") (pintype "passive"))
      (node (ref "IC10") (pin "5") (pinfunction "IN_5") (pintype "input"))
      (node (ref "IC6") (pin "4") (pinfunction "V+_4") (pintype "power_in"))
      (node (ref "IC9") (pin "4") (pinfunction "V+_4") (pintype "power_in"))
      (node (ref "J3") (pin "3") (pinfunction "3_3") (pintype "passive"))
      (node (ref "JP10") (pin "3") (pinfunction "3_3") (pintype "passive"))
      (node (ref "JP4") (pin "2") (pinfunction "2_2") (pintype "passive"))
      (node (ref "SJ11") (pin "2") (pinfunction "2_2") (pintype "passive"))
      (node (ref "SJ14") (pin "P$2") (pinfunction "2_P$2") (pintype "passive"))
      (node (ref "SJ2") (pin "2") (pinfunction "2_2") (pintype "passive"))
      (node (ref "SJ5") (pin "2") (pinfunction "2_2") (pintype "passive"))
      (node (ref "SJ8") (pin "2") (pinfunction "2_2") (pintype "passive"))
      (node (ref "U$2") (pin "6") (pinfunction "VDD_6") (pintype "power_in"))
      (node (ref "U$3") (pin "6") (pinfunction "VDD_6") (pintype "power_in"))
      (node (ref "U$4") (pin "6") (pinfunction "VDD_6") (pintype "power_in"))
      (node (ref "U$5") (pin "6") (pinfunction "VDD_6") (pintype "power_in"))
    )
    (net (code "4") (name "/AGND") (class "Default")
      (node (ref "U$1") (pin "AGND") (pinfunction "AGND_AGND") (pintype "power_in"))
    )
    (net (code "5") (name "/AVDD") (class "Default")
      (node (ref "U$1") (pin "AVDD") (pinfunction "AVDD_AVDD") (pintype "power_in"))
    )
    (net (code "6") (name "/CANH") (class "Default")
      (node (ref "IC7") (pin "7") (pinfunction "CANH_7") (pintype "bidirectional"))
      (node (ref "J1") (pin "1") (pinfunction "1_1") (pintype "passive"))
      (node (ref "J2") (pin "1") (pinfunction "1_1") (pintype "passive"))
      (node (ref "U$6") (pin "7") (pinfunction "CANH_7") (pintype "bidirectional"))
    )
    (net (code "7") (name "/CANL") (class "Default")
      (node (ref "IC7") (pin "6") (pinfunction "CANL_6") (pintype "bidirectional"))
      (node (ref "J1") (pin "2") (pinfunction "2_2") (pintype "passive"))
      (node (ref "J2") (pin "2") (pinfunction "2_2") (pintype "passive"))
      (node (ref "U$6") (pin "6") (pinfunction "CANL_6") (pintype "bidirectional"))
    )
    (net (code "8") (name "/G5V-3") (class "Default")
      (node (ref "U$1") (pin "PC12") (pinfunction "PC12_PC12") (pintype "bidirectional"))
    )
    (net (code "9") (name "/G5V-4") (class "Default")
      (node (ref "U$1") (pin "PD2") (pinfunction "PD2_PD2") (pintype "bidirectional"))
    )
    (net (code "10") (name "/G5V-5") (class "Default")
      (node (ref "U$1") (pin "PA15") (pinfunction "PA15_PA15") (pintype "bidirectional"))
    )
    (net (code "11") (name "/G5V-6") (class "Default")
      (node (ref "U$1") (pin "PF1-PH1") (pinfunction "PF1-PH1_PF1-PH1") (pintype "bidirectional"))
    )
    (net (code "12") (name "/TIN1") (class "Default")
      (node (ref "IC9") (pin "3") (pinfunction "+IN_3") (pintype "input"))
      (node (ref "U$1") (pin "PB2") (pinfunction "PB2_PB2") (pintype "bidirectional"))
      (node (ref "U$3") (pin "4") (pinfunction "I_4") (pintype "input"))
    )
    (net (code "13") (name "/TIN2") (class "Default")
      (node (ref "IC9") (pin "5") (pinfunction "+IN_5") (pintype "input"))
      (node (ref "U$1") (pin "PB1") (pinfunction "PB1_PB1") (pintype "bidirectional"))
      (node (ref "U$2") (pin "2") (pinfunction "I_2") (pintype "input"))
    )
    (net (code "14") (name "/TIN5") (class "Default")
      (node (ref "IC6") (pin "3") (pinfunction "+IN_3") (pintype "input"))
      (node (ref "U$1") (pin "PA4") (pinfunction "PA4_PA4") (pintype "bidirectional"))
      (node (ref "U$5") (pin "4") (pinfunction "I_4") (pintype "input"))
    )
    (net (code "15") (name "/TIN6") (class "Default")
      (node (ref "IC6") (pin "5") (pinfunction "+IN_5") (pintype "input"))
      (node (ref "U$1") (pin "PC0") (pinfunction "PC0_PC0") (pintype "bidirectional"))
      (node (ref "U$4") (pin "2") (pinfunction "I_2") (pintype "input"))
    )
    (net (code "16") (name "/TIN7") (class "Default")
      (node (ref "IC6") (pin "10") (pinfunction "+IN_10") (pintype "input"))
      (node (ref "U$1") (pin "PC3") (pinfunction "PC3_PC3") (pintype "bidirectional"))
      (node (ref "U$4") (pin "4") (pinfunction "I_4") (pintype "input"))
    )
    (net (code "17") (name "/TIN8") (class "Default")
      (node (ref "IC6") (pin "12") (pinfunction "+IN_12") (pintype "input"))
      (node (ref "U$1") (pin "PA0") (pinfunction "PA0_PA0") (pintype "bidirectional"))
      (node (ref "U$5") (pin "2") (pinfunction "I_2") (pintype "input"))
    )
    (net (code "18") (name "/U5V") (class "Default")
      (node (ref "U$1") (pin "U5V") (pinfunction "U5V_U5V") (pintype "power_in"))
    )
    (net (code "19") (name "/VBAT") (class "Default")
      (node (ref "U$1") (pin "VBAT") (pinfunction "VBAT_VBAT") (pintype "power_in"))
    )
    (net (code "20") (name "/VDD") (class "Default")
      (node (ref "U$1") (pin "VDD") (pinfunction "VDD_VDD") (pintype "power_in"))
    )
    (net (code "21") (name "CANRX") (class "Default")
      (node (ref "IC7") (pin "4") (pinfunction "RXD_4") (pintype "output"))
      (node (ref "U$1") (pin "PB8") (pinfunction "PB8_PB8") (pintype "bidirectional"))
      (node (ref "U$6") (pin "4") (pinfunction "RXD_4") (pintype "bidirectional"))
    )
    (net (code "22") (name "CANTX") (class "Default")
      (node (ref "IC7") (pin "1") (pinfunction "TXD_1") (pintype "input"))
      (node (ref "U$1") (pin "PB9") (pinfunction "PB9_PB9") (pintype "bidirectional"))
      (node (ref "U$6") (pin "1") (pinfunction "TXD_1") (pintype "bidirectional"))
    )
    (net (code "23") (name "E_CS") (class "Default")
      (node (ref "JP9") (pin "4") (pinfunction "4_4") (pintype "passive"))
      (node (ref "R23") (pin "2") (pinfunction "2_2") (pintype "passive"))
      (node (ref "U$1") (pin "PC10") (pinfunction "PC10_PC10") (pintype "bidirectional"))
    )
    (net (code "24") (name "E_LAT") (class "Default")
      (node (ref "JP10") (pin "1") (pinfunction "1_1") (pintype "passive"))
      (node (ref "R22") (pin "2") (pinfunction "2_2") (pintype "passive"))
      (node (ref "U$1") (pin "PC11") (pinfunction "PC11_PC11") (pintype "bidirectional"))
    )
    (net (code "25") (name "GND") (class "Default")
      (node (ref "AP1509") (pin "4") (pinfunction "SD_4") (pintype "bidirectional"))
      (node (ref "AP1509") (pin "5") (pinfunction "GND1_5") (pintype "power_in"))
      (node (ref "AP1509") (pin "6") (pinfunction "GND2_6") (pintype "power_in"))
      (node (ref "AP1509") (pin "7") (pinfunction "GND3_7") (pintype "power_in"))
      (node (ref "AP1509") (pin "8") (pinfunction "GND4_8") (pintype "power_in"))
      (node (ref "C1") (pin "2") (pinfunction "2_2") (pintype "passive"))
      (node (ref "C10") (pin "2") (pinfunction "2_2") (pintype "passive"))
      (node (ref "C12") (pin "2") (pinfunction "2_2") (pintype "passive"))
      (node (ref "C2") (pin "-") (pinfunction "-_-") (pintype "passive"))
      (node (ref "C3") (pin "2") (pinfunction "2_2") (pintype "passive"))
      (node (ref "C4") (pin "2") (pinfunction "2_2") (pintype "passive"))
      (node (ref "C5") (pin "2") (pinfunction "2_2") (pintype "passive"))
      (node (ref "C6") (pin "2") (pinfunction "2_2") (pintype "passive"))
      (node (ref "C7") (pin "2") (pinfunction "2_2") (pintype "passive"))
      (node (ref "C8") (pin "2") (pinfunction "2_2") (pintype "passive"))
      (node (ref "C9") (pin "2") (pinfunction "2_2") (pintype "passive"))
      (node (ref "D1") (pin "A") (pinfunction "A_A") (pintype "passive"))
      (node (ref "IC1") (pin "6") (pinfunction "INH_6") (pintype "input"))
      (node (ref "IC1") (pin "8") (pinfunction "GND_8") (pintype "power_in"))
      (node (ref "IC10") (pin "2") (pinfunction "GNDSIG_2") (pintype "input"))
      (node (ref "IC10") (pin "3") (pinfunction "~{ON/OFF}_3") (pintype "input"))
      (node (ref "IC10") (pin "4") (pinfunction "GND_4") (pintype "power_in"))
      (node (ref "IC3") (pin "13") (pinfunction "G_13") (pintype "input"))
      (node (ref "IC3") (pin "8") (pinfunction "GND_8") (pintype "power_in"))
      (node (ref "IC4") (pin "6") (pinfunction "INH_6") (pintype "input"))
      (node (ref "IC4") (pin "8") (pinfunction "GND_8") (pintype "power_in"))
      (node (ref "IC5") (pin "13") (pinfunction "G_13") (pintype "input"))
      (node (ref "IC5") (pin "8") (pinfunction "GND_8") (pintype "power_in"))
      (node (ref "IC6") (pin "11") (pinfunction "V-_11") (pintype "power_in"))
      (node (ref "IC7") (pin "2") (pinfunction "GND_2") (pintype "power_in"))
      (node (ref "IC9") (pin "11") (pinfunction "V-_11") (pintype "power_in"))
      (node (ref "J1") (pin "3") (pinfunction "3_3") (pintype "passive"))
      (node (ref "J1") (pin "6") (pinfunction "6_6") (pintype "passive"))
      (node (ref "J1") (pin "7") (pinfunction "7_7") (pintype "passive"))
      (node (ref "J2") (pin "3") (pinfunction "3_3") (pintype "passive"))
      (node (ref "J2") (pin "6") (pinfunction "6_6") (pintype "passive"))
      (node (ref "J2") (pin "7") (pinfunction "7_7") (pintype "passive"))
      (node (ref "J3") (pin "1") (pinfunction "1_1") (pintype "passive"))
      (node (ref "JP10") (pin "4") (pinfunction "4_4") (pintype "passive"))
      (node (ref "JP11") (pin "5") (pinfunction "5_5") (pintype "passive"))
      (node (ref "JP11") (pin "6") (pinfunction "6_6") (pintype "passive"))
      (node (ref "JP13") (pin "5") (pinfunction "5_5") (pintype "passive"))
      (node (ref "JP14") (pin "5") (pinfunction "5_5") (pintype "passive"))
      (node (ref "JP15") (pin "5") (pinfunction "5_5") (pintype "passive"))
      (node (ref "JP7") (pin "5") (pinfunction "5_5") (pintype "passive"))
      (node (ref "JP7") (pin "6") (pinfunction "6_6") (pintype "passive"))
      (node (ref "JP8") (pin "4") (pinfunction "4_4") (pintype "passive"))
      (node (ref "Q1") (pin "2") (pinfunction "S_2") (pintype "passive"))
      (node (ref "Q10") (pin "2") (pinfunction "S_2") (pintype "passive"))
      (node (ref "Q11") (pin "2") (pinfunction "S_2") (pintype "passive"))
      (node (ref "Q12") (pin "2") (pinfunction "S_2") (pintype "passive"))
      (node (ref "Q13") (pin "2") (pinfunction "S_2") (pintype "passive"))
      (node (ref "Q14") (pin "2") (pinfunction "S_2") (pintype "passive"))
      (node (ref "Q15") (pin "2") (pinfunction "S_2") (pintype "passive"))
      (node (ref "Q16") (pin "2") (pinfunction "S_2") (pintype "passive"))
      (node (ref "Q2") (pin "2") (pinfunction "S_2") (pintype "passive"))
      (node (ref "Q3") (pin "2") (pinfunction "S_2") (pintype "passive"))
      (node (ref "Q4") (pin "2") (pinfunction "S_2") (pintype "passive"))
      (node (ref "Q5") (pin "2") (pinfunction "S_2") (pintype "passive"))
      (node (ref "Q6") (pin "2") (pinfunction "S_2") (pintype "passive"))
      (node (ref "Q7") (pin "2") (pinfunction "S_2") (pintype "passive"))
      (node (ref "Q8") (pin "2") (pinfunction "S_2") (pintype "passive"))
      (node (ref "Q9") (pin "2") (pinfunction "S_2") (pintype "passive"))
      (node (ref "R2") (pin "1") (pinfunction "1_1") (pintype "passive"))
      (node (ref "R61") (pin "2") (pinfunction "2_2") (pintype "passive"))
      (node (ref "SJ12") (pin "2") (pinfunction "2_2") (pintype "passive"))
      (node (ref "SJ3") (pin "2") (pinfunction "2_2") (pintype "passive"))
      (node (ref "SJ6") (pin "2") (pinfunction "2_2") (pintype "passive"))
      (node (ref "SJ9") (pin "2") (pinfunction "2_2") (pintype "passive"))
      (node (ref "U$1") (pin "GND3") (pinfunction "GND3_GND3") (pintype "power_in"))
      (node (ref "U$1") (pin "GND4") (pinfunction "GND4_GND4") (pintype "power_in"))
      (node (ref "U$1") (pin "GND5") (pinfunction "GND5_GND5") (pintype "power_in"))
      (node (ref "U$1") (pin "GND6") (pinfunction "GND6_GND6") (pintype "power_in"))
      (node (ref "U$1") (pin "GND7") (pinfunction "GND7_GND7") (pintype "power_in"))
      (node (ref "U$1") (pin "GND8") (pinfunction "GND8_GND8") (pintype "power_in"))
      (node (ref "U$2") (pin "3") (pinfunction "VSS_3") (pintype "power_in"))
      (node (ref "U$3") (pin "3") (pinfunction "VSS_3") (pintype "power_in"))
      (node (ref "U$4") (pin "3") (pinfunction "VSS_3") (pintype "power_in"))
      (node (ref "U$5") (pin "3") (pinfunction "VSS_3") (pintype "power_in"))
      (node (ref "U$6") (pin "2") (pinfunction "VSS_2") (pintype "power_in"))
    )
    (net (code "26") (name "I2CSCL") (class "Default")
      (node (ref "JP8") (pin "2") (pinfunction "2_2") (pintype "passive"))
      (node (ref "R63") (pin "2") (pinfunction "2_2") (pintype "passive"))
      (node (ref "U$1") (pin "PB6") (pinfunction "PB6_PB6") (pintype "bidirectional"))
    )
    (net (code "27") (name "I2CSDA") (class "Default")
      (node (ref "JP8") (pin "1") (pinfunction "1_1") (pintype "passive"))
      (node (ref "R62") (pin "2") (pinfunction "2_2") (pintype "passive"))
      (node (ref "U$1") (pin "PB7") (pinfunction "PB7_PB7") (pintype "bidirectional"))
    )
    (net (code "28") (name "ILAT") (class "Default")
      (node (ref "IC1") (pin "15") (pinfunction "SH/~{LD}_15") (pintype "input"))
      (node (ref "IC4") (pin "15") (pinfunction "SH/~{LD}_15") (pintype "input"))
      (node (ref "U$1") (pin "PA6") (pinfunction "PA6_PA6") (pintype "bidirectional"))
    )
    (net (code "29") (name "MISO") (class "Default")
      (node (ref "JP9") (pin "1") (pinfunction "1_1") (pintype "passive"))
      (node (ref "U$1") (pin "PB4") (pinfunction "PB4_PB4") (pintype "bidirectional"))
    )
    (net (code "30") (name "MISO2") (class "Default")
      (node (ref "IC4") (pin "13") (pinfunction "QH_13") (pintype "output"))
      (node (ref "SJ13") (pin "2") (pinfunction "2_2") (pintype "passive"))
      (node (ref "U$1") (pin "PC2") (pinfunction "PC2_PC2") (pintype "bidirectional"))
    )
    (net (code "31") (name "MOSI") (class "Default")
      (node (ref "IC5") (pin "14") (pinfunction "SER_14") (pintype "input"))
      (node (ref "R20") (pin "1") (pinfunction "1_1") (pintype "passive"))
      (node (ref "SJ15") (pin "1") (pinfunction "1_1") (pintype "passive"))
      (node (ref "SJ17") (pin "P$2") (pinfunction "2_P$2") (pintype "passive"))
      (node (ref "U$1") (pin "PB5") (pinfunction "PB5_PB5") (pintype "bidirectional"))
    )
    (net (code "32") (name "Net-(AP1509-VOUT)") (class "Default")
      (node (ref "AP1509") (pin "2") (pinfunction "VOUT_2") (pintype "bidirectional"))
      (node (ref "D1") (pin "C") (pinfunction "C_C") (pintype "passive"))
      (node (ref "IC10") (pin "7") (pinfunction "OUT_7") (pintype "passive"))
      (node (ref "L1") (pin "2") (pinfunction "2_2") (pintype "passive"))
    )
    (net (code "33") (name "Net-(D2-PadA)") (class "Default")
      (node (ref "D2") (pin "A") (pinfunction "A_A") (pintype "passive"))
      (node (ref "JP4") (pin "4") (pinfunction "4_4") (pintype "passive"))
    )
    (net (code "34") (name "Net-(D2-PadC)") (class "Default")
      (node (ref "D2") (pin "C") (pinfunction "C_C") (pintype "passive"))
      (node (ref "JP4") (pin "1") (pinfunction "1_1") (pintype "passive"))
    )
    (net (code "35") (name "Net-(IC1A-A)") (class "Default")
      (node (ref "IC1") (pin "2") (pinfunction "A_2") (pintype "input"))
      (node (ref "R36") (pin "1") (pinfunction "1_1") (pintype "passive"))
      (node (ref "RN4") (pin "9") (pinfunction "2_9") (pintype "passive"))
    )
    (net (code "36") (name "Net-(IC1A-B)") (class "Default")
      (node (ref "IC1") (pin "3") (pinfunction "B_3") (pintype "input"))
      (node (ref "R37") (pin "1") (pinfunction "1_1") (pintype "passive"))
      (node (ref "RN4") (pin "10") (pinfunction "2_10") (pintype "passive"))
    )
    (net (code "37") (name "Net-(IC1A-C)") (class "Default")
      (node (ref "IC1") (pin "4") (pinfunction "C_4") (pintype "input"))
      (node (ref "R38") (pin "1") (pinfunction "1_1") (pintype "passive"))
      (node (ref "RN4") (pin "11") (pinfunction "2_11") (pintype "passive"))
    )
    (net (code "38") (name "Net-(IC1A-D)") (class "Default")
      (node (ref "IC1") (pin "5") (pinfunction "D_5") (pintype "input"))
      (node (ref "R39") (pin "1") (pinfunction "1_1") (pintype "passive"))
      (node (ref "RN4") (pin "12") (pinfunction "2_12") (pintype "passive"))
    )
    (net (code "39") (name "Net-(IC1A-E)") (class "Default")
      (node (ref "IC1") (pin "10") (pinfunction "E_10") (pintype "input"))
      (node (ref "R41") (pin "1") (pinfunction "1_1") (pintype "passive"))
      (node (ref "RN4") (pin "13") (pinfunction "2_13") (pintype "passive"))
    )
    (net (code "40") (name "Net-(IC1A-F)") (class "Default")
      (node (ref "IC1") (pin "11") (pinfunction "F_11") (pintype "input"))
      (node (ref "R42") (pin "1") (pinfunction "1_1") (pintype "passive"))
      (node (ref "RN4") (pin "14") (pinfunction "2_14") (pintype "passive"))
    )
    (net (code "41") (name "Net-(IC1A-G)") (class "Default")
      (node (ref "IC1") (pin "12") (pinfunction "G_12") (pintype "input"))
      (node (ref "R43") (pin "1") (pinfunction "1_1") (pintype "passive"))
      (node (ref "RN4") (pin "15") (pinfunction "2_15") (pintype "passive"))
    )
    (net (code "42") (name "Net-(IC1A-H)") (class "Default")
      (node (ref "IC1") (pin "14") (pinfunction "H_14") (pintype "input"))
      (node (ref "R44") (pin "1") (pinfunction "1_1") (pintype "passive"))
      (node (ref "RN4") (pin "16") (pinfunction "2_16") (pintype "passive"))
    )
    (net (code "43") (name "Net-(IC2-CD+)") (class "Default")
      (node (ref "IC2") (pin "10") (pinfunction "CD+_10") (pintype "passive"))
      (node (ref "SJ4") (pin "1") (pinfunction "1_1") (pintype "passive"))
      (node (ref "SJ5") (pin "1") (pinfunction "1_1") (pintype "passive"))
      (node (ref "SJ6") (pin "1") (pinfunction "1_1") (pintype "passive"))
    )
    (net (code "44") (name "Net-(IC2-GND)") (class "Default")
      (node (ref "IC2") (pin "9") (pinfunction "GND_9") (pintype "power_in"))
      (node (ref "SJ1") (pin "1") (pinfunction "1_1") (pintype "passive"))
      (node (ref "SJ2") (pin "1") (pinfunction "1_1") (pintype "passive"))
      (node (ref "SJ3") (pin "1") (pinfunction "1_1") (pintype "passive"))
    )
    (net (code "45") (name "Net-(IC2-I1)") (class "Default")
      (node (ref "IC2") (pin "1") (pinfunction "I1_1") (pintype "input"))
      (node (ref "IC5") (pin "15") (pinfunction "QA_15") (pintype "tri_state"))
      (node (ref "R3") (pin "1") (pinfunction "1_1") (pintype "passive"))
    )
    (net (code "46") (name "Net-(IC2-I2)") (class "Default")
      (node (ref "IC2") (pin "2") (pinfunction "I2_2") (pintype "input"))
      (node (ref "IC5") (pin "1") (pinfunction "QB_1") (pintype "tri_state"))
      (node (ref "R4") (pin "1") (pinfunction "1_1") (pintype "passive"))
    )
    (net (code "47") (name "Net-(IC2-I3)") (class "Default")
      (node (ref "IC2") (pin "3") (pinfunction "I3_3") (pintype "input"))
      (node (ref "IC5") (pin "2") (pinfunction "QC_2") (pintype "tri_state"))
      (node (ref "R5") (pin "1") (pinfunction "1_1") (pintype "passive"))
    )
    (net (code "48") (name "Net-(IC2-I4)") (class "Default")
      (node (ref "IC2") (pin "4") (pinfunction "I4_4") (pintype "input"))
      (node (ref "IC5") (pin "3") (pinfunction "QD_3") (pintype "tri_state"))
      (node (ref "R6") (pin "1") (pinfunction "1_1") (pintype "passive"))
    )
    (net (code "49") (name "Net-(IC2-I5)") (class "Default")
      (node (ref "IC2") (pin "5") (pinfunction "I5_5") (pintype "input"))
      (node (ref "IC5") (pin "4") (pinfunction "QE_4") (pintype "tri_state"))
      (node (ref "R7") (pin "1") (pinfunction "1_1") (pintype "passive"))
    )
    (net (code "50") (name "Net-(IC2-I6)") (class "Default")
      (node (ref "IC2") (pin "6") (pinfunction "I6_6") (pintype "input"))
      (node (ref "IC5") (pin "5") (pinfunction "QF_5") (pintype "tri_state"))
      (node (ref "R8") (pin "1") (pinfunction "1_1") (pintype "passive"))
    )
    (net (code "51") (name "Net-(IC2-I7)") (class "Default")
      (node (ref "IC2") (pin "7") (pinfunction "I7_7") (pintype "input"))
      (node (ref "IC5") (pin "6") (pinfunction "QG_6") (pintype "tri_state"))
      (node (ref "R9") (pin "1") (pinfunction "1_1") (pintype "passive"))
    )
    (net (code "52") (name "Net-(IC2-I8)") (class "Default")
      (node (ref "IC2") (pin "8") (pinfunction "I8_8") (pintype "input"))
      (node (ref "IC5") (pin "7") (pinfunction "QH_7") (pintype "tri_state"))
      (node (ref "R10") (pin "1") (pinfunction "1_1") (pintype "passive"))
    )
    (net (code "53") (name "Net-(IC2-O1)") (class "Default")
      (node (ref "IC2") (pin "18") (pinfunction "O1_18") (pintype "open_collector"))
      (node (ref "JP1") (pin "1") (pinfunction "1_1") (pintype "passive"))
      (node (ref "Q1") (pin "3") (pinfunction "D_3") (pintype "passive"))
    )
    (net (code "54") (name "Net-(IC2-O2)") (class "Default")
      (node (ref "IC2") (pin "17") (pinfunction "O2_17") (pintype "open_collector"))
      (node (ref "JP1") (pin "2") (pinfunction "2_2") (pintype "passive"))
      (node (ref "Q2") (pin "3") (pinfunction "D_3") (pintype "passive"))
    )
    (net (code "55") (name "Net-(IC2-O3)") (class "Default")
      (node (ref "IC2") (pin "16") (pinfunction "O3_16") (pintype "open_collector"))
      (node (ref "JP1") (pin "3") (pinfunction "3_3") (pintype "passive"))
      (node (ref "Q3") (pin "3") (pinfunction "D_3") (pintype "passive"))
    )
    (net (code "56") (name "Net-(IC2-O4)") (class "Default")
      (node (ref "IC2") (pin "15") (pinfunction "O4_15") (pintype "open_collector"))
      (node (ref "JP1") (pin "4") (pinfunction "4_4") (pintype "passive"))
      (node (ref "Q4") (pin "3") (pinfunction "D_3") (pintype "passive"))
    )
    (net (code "57") (name "Net-(IC2-O5)") (class "Default")
      (node (ref "IC2") (pin "14") (pinfunction "O5_14") (pintype "open_collector"))
      (node (ref "JP1") (pin "5") (pinfunction "5_5") (pintype "passive"))
      (node (ref "Q5") (pin "3") (pinfunction "D_3") (pintype "passive"))
    )
    (net (code "58") (name "Net-(IC2-O6)") (class "Default")
      (node (ref "IC2") (pin "13") (pinfunction "O6_13") (pintype "open_collector"))
      (node (ref "JP1") (pin "6") (pinfunction "6_6") (pintype "passive"))
      (node (ref "Q6") (pin "3") (pinfunction "D_3") (pintype "passive"))
    )
    (net (code "59") (name "Net-(IC2-O7)") (class "Default")
      (node (ref "IC2") (pin "12") (pinfunction "O7_12") (pintype "open_collector"))
      (node (ref "JP1") (pin "7") (pinfunction "7_7") (pintype "passive"))
      (node (ref "Q7") (pin "3") (pinfunction "D_3") (pintype "passive"))
    )
    (net (code "60") (name "Net-(IC2-O8)") (class "Default")
      (node (ref "IC2") (pin "11") (pinfunction "O8_11") (pintype "open_collector"))
      (node (ref "JP1") (pin "8") (pinfunction "8_8") (pintype "passive"))
      (node (ref "Q8") (pin "3") (pinfunction "D_3") (pintype "passive"))
    )
    (net (code "61") (name "Net-(IC3A-QA)") (class "Default")
      (node (ref "IC3") (pin "15") (pinfunction "QA_15") (pintype "tri_state"))
      (node (ref "IC8") (pin "1") (pinfunction "I1_1") (pintype "input"))
      (node (ref "R11") (pin "1") (pinfunction "1_1") (pintype "passive"))
    )
    (net (code "62") (name "Net-(IC3A-QB)") (class "Default")
      (node (ref "IC3") (pin "1") (pinfunction "QB_1") (pintype "tri_state"))
      (node (ref "IC8") (pin "2") (pinfunction "I2_2") (pintype "input"))
      (node (ref "R12") (pin "1") (pinfunction "1_1") (pintype "passive"))
    )
    (net (code "63") (name "Net-(IC3A-QC)") (class "Default")
      (node (ref "IC3") (pin "2") (pinfunction "QC_2") (pintype "tri_state"))
      (node (ref "IC8") (pin "3") (pinfunction "I3_3") (pintype "input"))
      (node (ref "R13") (pin "1") (pinfunction "1_1") (pintype "passive"))
    )
    (net (code "64") (name "Net-(IC3A-QD)") (class "Default")
      (node (ref "IC3") (pin "3") (pinfunction "QD_3") (pintype "tri_state"))
      (node (ref "IC8") (pin "4") (pinfunction "I4_4") (pintype "input"))
      (node (ref "R14") (pin "1") (pinfunction "1_1") (pintype "passive"))
    )
    (net (code "65") (name "Net-(IC3A-QE)") (class "Default")
      (node (ref "IC3") (pin "4") (pinfunction "QE_4") (pintype "tri_state"))
      (node (ref "IC8") (pin "5") (pinfunction "I5_5") (pintype "input"))
      (node (ref "R15") (pin "1") (pinfunction "1_1") (pintype "passive"))
    )
    (net (code "66") (name "Net-(IC3A-QF)") (class "Default")
      (node (ref "IC3") (pin "5") (pinfunction "QF_5") (pintype "tri_state"))
      (node (ref "IC8") (pin "6") (pinfunction "I6_6") (pintype "input"))
      (node (ref "R16") (pin "1") (pinfunction "1_1") (pintype "passive"))
    )
    (net (code "67") (name "Net-(IC3A-QG)") (class "Default")
      (node (ref "IC3") (pin "6") (pinfunction "QG_6") (pintype "tri_state"))
      (node (ref "IC8") (pin "7") (pinfunction "I7_7") (pintype "input"))
      (node (ref "R17") (pin "1") (pinfunction "1_1") (pintype "passive"))
    )
    (net (code "68") (name "Net-(IC3A-QH)") (class "Default")
      (node (ref "IC3") (pin "7") (pinfunction "QH_7") (pintype "tri_state"))
      (node (ref "IC8") (pin "8") (pinfunction "I8_8") (pintype "input"))
      (node (ref "R18") (pin "1") (pinfunction "1_1") (pintype "passive"))
    )
    (net (code "69") (name "Net-(IC4A-A)") (class "Default")
      (node (ref "IC4") (pin "2") (pinfunction "A_2") (pintype "input"))
      (node (ref "R28") (pin "1") (pinfunction "1_1") (pintype "passive"))
      (node (ref "RN1") (pin "9") (pinfunction "2_9") (pintype "passive"))
    )
    (net (code "70") (name "Net-(IC4A-B)") (class "Default")
      (node (ref "IC4") (pin "3") (pinfunction "B_3") (pintype "input"))
      (node (ref "R29") (pin "1") (pinfunction "1_1") (pintype "passive"))
      (node (ref "RN1") (pin "10") (pinfunction "2_10") (pintype "passive"))
    )
    (net (code "71") (name "Net-(IC4A-C)") (class "Default")
      (node (ref "IC4") (pin "4") (pinfunction "C_4") (pintype "input"))
      (node (ref "R30") (pin "1") (pinfunction "1_1") (pintype "passive"))
      (node (ref "RN1") (pin "11") (pinfunction "2_11") (pintype "passive"))
    )
    (net (code "72") (name "Net-(IC4A-D)") (class "Default")
      (node (ref "IC4") (pin "5") (pinfunction "D_5") (pintype "input"))
      (node (ref "R31") (pin "1") (pinfunction "1_1") (pintype "passive"))
      (node (ref "RN1") (pin "12") (pinfunction "2_12") (pintype "passive"))
    )
    (net (code "73") (name "Net-(IC4A-E)") (class "Default")
      (node (ref "IC4") (pin "10") (pinfunction "E_10") (pintype "input"))
      (node (ref "R32") (pin "1") (pinfunction "1_1") (pintype "passive"))
      (node (ref "RN1") (pin "13") (pinfunction "2_13") (pintype "passive"))
    )
    (net (code "74") (name "Net-(IC4A-F)") (class "Default")
      (node (ref "IC4") (pin "11") (pinfunction "F_11") (pintype "input"))
      (node (ref "R33") (pin "1") (pinfunction "1_1") (pintype "passive"))
      (node (ref "RN1") (pin "14") (pinfunction "2_14") (pintype "passive"))
    )
    (net (code "75") (name "Net-(IC4A-G)") (class "Default")
      (node (ref "IC4") (pin "12") (pinfunction "G_12") (pintype "input"))
      (node (ref "R34") (pin "1") (pinfunction "1_1") (pintype "passive"))
      (node (ref "RN1") (pin "15") (pinfunction "2_15") (pintype "passive"))
    )
    (net (code "76") (name "Net-(IC4A-H)") (class "Default")
      (node (ref "IC4") (pin "14") (pinfunction "H_14") (pintype "input"))
      (node (ref "R35") (pin "1") (pinfunction "1_1") (pintype "passive"))
      (node (ref "RN1") (pin "16") (pinfunction "2_16") (pintype "passive"))
    )
    (net (code "77") (name "Net-(IC6A--IN)") (class "Default")
      (node (ref "IC6") (pin "13") (pinfunction "-IN_13") (pintype "input"))
      (node (ref "IC6") (pin "2") (pinfunction "-IN_2") (pintype "input"))
      (node (ref "IC6") (pin "6") (pinfunction "-IN_6") (pintype "input"))
      (node (ref "IC6") (pin "9") (pinfunction "-IN_9") (pintype "input"))
      (node (ref "IC9") (pin "13") (pinfunction "-IN_13") (pintype "input"))
      (node (ref "IC9") (pin "2") (pinfunction "-IN_2") (pintype "input"))
      (node (ref "IC9") (pin "6") (pinfunction "-IN_6") (pintype "input"))
      (node (ref "IC9") (pin "9") (pinfunction "-IN_9") (pintype "input"))
      (node (ref "R1") (pin "1") (pinfunction "1_1") (pintype "passive"))
      (node (ref "R2") (pin "2") (pinfunction "2_2") (pintype "passive"))
    )
    (net (code "78") (name "Net-(IC6A-OUT)") (class "Default")
      (node (ref "IC6") (pin "1") (pinfunction "OUT_1") (pintype "output"))
      (node (ref "JP15") (pin "3") (pinfunction "3_3") (pintype "passive"))
      (node (ref "JP5") (pin "3") (pinfunction "3_3") (pintype "passive"))
      (node (ref "U$5") (pin "5") (pinfunction "O_5") (pintype "output"))
    )
    (net (code "79") (name "Net-(IC6B-OUT)") (class "Default")
      (node (ref "IC6") (pin "7") (pinfunction "OUT_7") (pintype "output"))
      (node (ref "JP15") (pin "1") (pinfunction "1_1") (pintype "passive"))
      (node (ref "JP5") (pin "1") (pinfunction "1_1") (pintype "passive"))
      (node (ref "U$4") (pin "7") (pinfunction "O_7") (pintype "output"))
    )
    (net (code "80") (name "Net-(IC6C-OUT)") (class "Default")
      (node (ref "IC6") (pin "8") (pinfunction "OUT_8") (pintype "output"))
      (node (ref "JP15") (pin "2") (pinfunction "2_2") (pintype "passive"))
      (node (ref "JP5") (pin "2") (pinfunction "2_2") (pintype "passive"))
      (node (ref "U$4") (pin "5") (pinfunction "O_5") (pintype "output"))
    )
    (net (code "81") (name "Net-(IC6D-OUT)") (class "Default")
      (node (ref "IC6") (pin "14") (pinfunction "OUT_14") (pintype "output"))
      (node (ref "JP15") (pin "4") (pinfunction "4_4") (pintype "passive"))
      (node (ref "JP5") (pin "4") (pinfunction "4_4") (pintype "passive"))
      (node (ref "U$5") (pin "7") (pinfunction "O_7") (pintype "output"))
    )
    (net (code "82") (name "Net-(IC7-RS)") (class "Default")
      (node (ref "IC7") (pin "8") (pinfunction "RS_8") (pintype "input"))
      (node (ref "R61") (pin "1") (pinfunction "1_1") (pintype "passive"))
      (node (ref "U$6") (pin "8") (pinfunction "RS_8") (pintype "bidirectional"))
    )
    (net (code "83") (name "Net-(IC7-VREF)") (class "Default")
      (node (ref "IC7") (pin "5") (pinfunction "VREF_5") (pintype "output"))
      (node (ref "SJ18") (pin "P$2") (pinfunction "2_P$2") (pintype "passive"))
      (node (ref "U$6") (pin "5") (pinfunction "VREF_5") (pintype "bidirectional"))
    )
    (net (code "84") (name "Net-(IC8-CD+)") (class "Default")
      (node (ref "IC8") (pin "10") (pinfunction "CD+_10") (pintype "passive"))
      (node (ref "SJ10") (pin "1") (pinfunction "1_1") (pintype "passive"))
      (node (ref "SJ11") (pin "1") (pinfunction "1_1") (pintype "passive"))
      (node (ref "SJ12") (pin "1") (pinfunction "1_1") (pintype "passive"))
    )
    (net (code "85") (name "Net-(IC8-GND)") (class "Default")
      (node (ref "IC8") (pin "9") (pinfunction "GND_9") (pintype "power_in"))
      (node (ref "SJ7") (pin "1") (pinfunction "1_1") (pintype "passive"))
      (node (ref "SJ8") (pin "1") (pinfunction "1_1") (pintype "passive"))
      (node (ref "SJ9") (pin "1") (pinfunction "1_1") (pintype "passive"))
    )
    (net (code "86") (name "Net-(IC8-O1)") (class "Default")
      (node (ref "IC8") (pin "18") (pinfunction "O1_18") (pintype "open_collector"))
      (node (ref "JP6") (pin "1") (pinfunction "1_1") (pintype "passive"))
      (node (ref "Q9") (pin "3") (pinfunction "D_3") (pintype "passive"))
    )
    (net (code "87") (name "Net-(IC8-O2)") (class "Default")
      (node (ref "IC8") (pin "17") (pinfunction "O2_17") (pintype "open_collector"))
      (node (ref "JP6") (pin "2") (pinfunction "2_2") (pintype "passive"))
      (node (ref "Q10") (pin "3") (pinfunction "D_3") (pintype "passive"))
    )
    (net (code "88") (name "Net-(IC8-O3)") (class "Default")
      (node (ref "IC8") (pin "16") (pinfunction "O3_16") (pintype "open_collector"))
      (node (ref "JP6") (pin "3") (pinfunction "3_3") (pintype "passive"))
      (node (ref "Q11") (pin "3") (pinfunction "D_3") (pintype "passive"))
    )
    (net (code "89") (name "Net-(IC8-O4)") (class "Default")
      (node (ref "IC8") (pin "15") (pinfunction "O4_15") (pintype "open_collector"))
      (node (ref "JP6") (pin "4") (pinfunction "4_4") (pintype "passive"))
      (node (ref "Q12") (pin "3") (pinfunction "D_3") (pintype "passive"))
    )
    (net (code "90") (name "Net-(IC8-O5)") (class "Default")
      (node (ref "IC8") (pin "14") (pinfunction "O5_14") (pintype "open_collector"))
      (node (ref "JP6") (pin "5") (pinfunction "5_5") (pintype "passive"))
      (node (ref "Q13") (pin "3") (pinfunction "D_3") (pintype "passive"))
    )
    (net (code "91") (name "Net-(IC8-O6)") (class "Default")
      (node (ref "IC8") (pin "13") (pinfunction "O6_13") (pintype "open_collector"))
      (node (ref "JP6") (pin "6") (pinfunction "6_6") (pintype "passive"))
      (node (ref "Q14") (pin "3") (pinfunction "D_3") (pintype "passive"))
    )
    (net (code "92") (name "Net-(IC8-O7)") (class "Default")
      (node (ref "IC8") (pin "12") (pinfunction "O7_12") (pintype "open_collector"))
      (node (ref "JP6") (pin "7") (pinfunction "7_7") (pintype "passive"))
      (node (ref "Q15") (pin "3") (pinfunction "D_3") (pintype "passive"))
    )
    (net (code "93") (name "Net-(IC8-O8)") (class "Default")
      (node (ref "IC8") (pin "11") (pinfunction "O8_11") (pintype "open_collector"))
      (node (ref "JP6") (pin "8") (pinfunction "8_8") (pintype "passive"))
      (node (ref "Q16") (pin "3") (pinfunction "D_3") (pintype "passive"))
    )
    (net (code "94") (name "Net-(IC9A-OUT)") (class "Default")
      (node (ref "IC9") (pin "1") (pinfunction "OUT_1") (pintype "output"))
      (node (ref "JP15") (pin "9") (pinfunction "9_9") (pintype "passive"))
      (node (ref "JP5") (pin "7") (pinfunction "7_7") (pintype "passive"))
      (node (ref "U$3") (pin "5") (pinfunction "O_5") (pintype "output"))
    )
    (net (code "95") (name "Net-(IC9B-OUT)") (class "Default")
      (node (ref "IC9") (pin "7") (pinfunction "OUT_7") (pintype "output"))
      (node (ref "JP15") (pin "7") (pinfunction "7_7") (pintype "passive"))
      (node (ref "JP5") (pin "5") (pinfunction "5_5") (pintype "passive"))
      (node (ref "U$2") (pin "7") (pinfunction "O_7") (pintype "output"))
    )
    (net (code "96") (name "Net-(IC9C-OUT)") (class "Default")
      (node (ref "IC9") (pin "8") (pinfunction "OUT_8") (pintype "output"))
      (node (ref "JP15") (pin "8") (pinfunction "8_8") (pintype "passive"))
      (node (ref "JP5") (pin "6") (pinfunction "6_6") (pintype "passive"))
      (node (ref "U$2") (pin "5") (pinfunction "O_5") (pintype "output"))
    )
    (net (code "97") (name "Net-(IC9D-OUT)") (class "Default")
      (node (ref "IC9") (pin "14") (pinfunction "OUT_14") (pintype "output"))
      (node (ref "JP15") (pin "10") (pinfunction "10_10") (pintype "passive"))
      (node (ref "JP5") (pin "8") (pinfunction "8_8") (pintype "passive"))
      (node (ref "U$3") (pin "7") (pinfunction "O_7") (pintype "output"))
    )
    (net (code "98") (name "Net-(J1-Pad4)") (class "Default")
      (node (ref "J1") (pin "4") (pinfunction "4_4") (pintype "passive"))
      (node (ref "J2") (pin "4") (pinfunction "4_4") (pintype "passive"))
    )
    (net (code "99") (name "Net-(J1-Pad5)") (class "Default")
      (node (ref "J1") (pin "5") (pinfunction "5_5") (pintype "passive"))
      (node (ref "J2") (pin "5") (pinfunction "5_5") (pintype "passive"))
    )
    (net (code "100") (name "Net-(J1-Pad8)") (class "Default")
      (node (ref "J1") (pin "8") (pinfunction "8_8") (pintype "passive"))
      (node (ref "J2") (pin "8") (pinfunction "8_8") (pintype "passive"))
      (node (ref "R40") (pin "1") (pinfunction "1_1") (pintype "passive"))
    )
    (net (code "101") (name "Net-(JP4-Pad3)") (class "Default")
      (node (ref "JP4") (pin "3") (pinfunction "3_3") (pintype "passive"))
      (node (ref "R40") (pin "2") (pinfunction "2_2") (pintype "passive"))
    )
    (net (code "102") (name "Net-(JP13-Pad1)") (class "Default")
      (node (ref "JP13") (pin "1") (pinfunction "1_1") (pintype "passive"))
      (node (ref "JP3") (pin "1") (pinfunction "1_1") (pintype "passive"))
      (node (ref "R44") (pin "2") (pinfunction "2_2") (pintype "passive"))
      (node (ref "R53") (pin "2") (pinfunction "2_2") (pintype "passive"))
      (node (ref "RN4") (pin "1") (pinfunction "1_1") (pintype "passive"))
      (node (ref "RN5") (pin "9") (pinfunction "9_9") (pintype "passive"))
    )
    (net (code "103") (name "Net-(JP14-Pad1)") (class "Default")
      (node (ref "JP14") (pin "1") (pinfunction "1_1") (pintype "passive"))
      (node (ref "JP2") (pin "1") (pinfunction "1_1") (pintype "passive"))
      (node (ref "R35") (pin "2") (pinfunction "2_2") (pintype "passive"))
      (node (ref "R45") (pin "2") (pinfunction "2_2") (pintype "passive"))
      (node (ref "RN1") (pin "1") (pinfunction "1_1") (pintype "passive"))
      (node (ref "RN2") (pin "9") (pinfunction "9_9") (pintype "passive"))
    )
    (net (code "104") (name "Net-(Q1-G)") (class "Default")
      (node (ref "Q1") (pin "1") (pinfunction "G_1") (pintype "passive"))
      (node (ref "R3") (pin "2") (pinfunction "2_2") (pintype "passive"))
    )
    (net (code "105") (name "Net-(Q2-G)") (class "Default")
      (node (ref "Q2") (pin "1") (pinfunction "G_1") (pintype "passive"))
      (node (ref "R4") (pin "2") (pinfunction "2_2") (pintype "passive"))
    )
    (net (code "106") (name "Net-(Q3-G)") (class "Default")
      (node (ref "Q3") (pin "1") (pinfunction "G_1") (pintype "passive"))
      (node (ref "R5") (pin "2") (pinfunction "2_2") (pintype "passive"))
    )
    (net (code "107") (name "Net-(Q4-G)") (class "Default")
      (node (ref "Q4") (pin "1") (pinfunction "G_1") (pintype "passive"))
      (node (ref "R6") (pin "2") (pinfunction "2_2") (pintype "passive"))
    )
    (net (code "108") (name "Net-(Q5-G)") (class "Default")
      (node (ref "Q5") (pin "1") (pinfunction "G_1") (pintype "passive"))
      (node (ref "R7") (pin "2") (pinfunction "2_2") (pintype "passive"))
    )
    (net (code "109") (name "Net-(Q6-G)") (class "Default")
      (node (ref "Q6") (pin "1") (pinfunction "G_1") (pintype "passive"))
      (node (ref "R8") (pin "2") (pinfunction "2_2") (pintype "passive"))
    )
    (net (code "110") (name "Net-(Q7-G)") (class "Default")
      (node (ref "Q7") (pin "1") (pinfunction "G_1") (pintype "passive"))
      (node (ref "R9") (pin "2") (pinfunction "2_2") (pintype "passive"))
    )
    (net (code "111") (name "Net-(Q8-G)") (class "Default")
      (node (ref "Q8") (pin "1") (pinfunction "G_1") (pintype "passive"))
      (node (ref "R10") (pin "2") (pinfunction "2_2") (pintype "passive"))
    )
    (net (code "112") (name "Net-(Q9-G)") (class "Default")
      (node (ref "Q9") (pin "1") (pinfunction "G_1") (pintype "passive"))
      (node (ref "R11") (pin "2") (pinfunction "2_2") (pintype "passive"))
    )
    (net (code "113") (name "Net-(Q10-G)") (class "Default")
      (node (ref "Q10") (pin "1") (pinfunction "G_1") (pintype "passive"))
      (node (ref "R12") (pin "2") (pinfunction "2_2") (pintype "passive"))
    )
    (net (code "114") (name "Net-(Q11-G)") (class "Default")
      (node (ref "Q11") (pin "1") (pinfunction "G_1") (pintype "passive"))
      (node (ref "R13") (pin "2") (pinfunction "2_2") (pintype "passive"))
    )
    (net (code "115") (name "Net-(Q12-G)") (class "Default")
      (node (ref "Q12") (pin "1") (pinfunction "G_1") (pintype "passive"))
      (node (ref "R14") (pin "2") (pinfunction "2_2") (pintype "passive"))
    )
    (net (code "116") (name "Net-(Q13-G)") (class "Default")
      (node (ref "Q13") (pin "1") (pinfunction "G_1") (pintype "passive"))
      (node (ref "R15") (pin "2") (pinfunction "2_2") (pintype "passive"))
    )
    (net (code "117") (name "Net-(Q14-G)") (class "Default")
      (node (ref "Q14") (pin "1") (pinfunction "G_1") (pintype "passive"))
      (node (ref "R16") (pin "2") (pinfunction "2_2") (pintype "passive"))
    )
    (net (code "118") (name "Net-(Q15-G)") (class "Default")
      (node (ref "Q15") (pin "1") (pinfunction "G_1") (pintype "passive"))
      (node (ref "R17") (pin "2") (pinfunction "2_2") (pintype "passive"))
    )
    (net (code "119") (name "Net-(Q16-G)") (class "Default")
      (node (ref "Q16") (pin "1") (pinfunction "G_1") (pintype "passive"))
      (node (ref "R18") (pin "2") (pinfunction "2_2") (pintype "passive"))
    )
    (net (code "120") (name "Net-(RN1B-1)") (class "Default")
      (node (ref "JP14") (pin "2") (pinfunction "2_2") (pintype "passive"))
      (node (ref "JP2") (pin "2") (pinfunction "2_2") (pintype "passive"))
      (node (ref "R34") (pin "2") (pinfunction "2_2") (pintype "passive"))
      (node (ref "R46") (pin "1") (pinfunction "1_1") (pintype "passive"))
      (node (ref "RN1") (pin "2") (pinfunction "1_2") (pintype "passive"))
      (node (ref "RN2") (pin "8") (pinfunction "8_8") (pintype "passive"))
    )
    (net (code "121") (name "Net-(RN1C-1)") (class "Default")
      (node (ref "JP14") (pin "3") (pinfunction "3_3") (pintype "passive"))
      (node (ref "JP2") (pin "3") (pinfunction "3_3") (pintype "passive"))
      (node (ref "R33") (pin "2") (pinfunction "2_2") (pintype "passive"))
      (node (ref "R47") (pin "1") (pinfunction "1_1") (pintype "passive"))
      (node (ref "RN1") (pin "3") (pinfunction "1_3") (pintype "passive"))
      (node (ref "RN2") (pin "7") (pinfunction "7_7") (pintype "passive"))
    )
    (net (code "122") (name "Net-(RN1D-1)") (class "Default")
      (node (ref "JP14") (pin "4") (pinfunction "4_4") (pintype "passive"))
      (node (ref "JP2") (pin "4") (pinfunction "4_4") (pintype "passive"))
      (node (ref "R32") (pin "2") (pinfunction "2_2") (pintype "passive"))
      (node (ref "R48") (pin "1") (pinfunction "1_1") (pintype "passive"))
      (node (ref "RN1") (pin "4") (pinfunction "1_4") (pintype "passive"))
      (node (ref "RN2") (pin "6") (pinfunction "6_6") (pintype "passive"))
    )
    (net (code "123") (name "Net-(RN1E-1)") (class "Default")
      (node (ref "JP14") (pin "7") (pinfunction "7_7") (pintype "passive"))
      (node (ref "JP2") (pin "5") (pinfunction "5_5") (pintype "passive"))
      (node (ref "R31") (pin "2") (pinfunction "2_2") (pintype "passive"))
      (node (ref "R49") (pin "1") (pinfunction "1_1") (pintype "passive"))
      (node (ref "RN1") (pin "5") (pinfunction "1_5") (pintype "passive"))
      (node (ref "RN2") (pin "5") (pinfunction "5_5") (pintype "passive"))
    )
    (net (code "124") (name "Net-(RN1F-1)") (class "Default")
      (node (ref "JP14") (pin "8") (pinfunction "8_8") (pintype "passive"))
      (node (ref "JP2") (pin "6") (pinfunction "6_6") (pintype "passive"))
      (node (ref "R30") (pin "2") (pinfunction "2_2") (pintype "passive"))
      (node (ref "R50") (pin "1") (pinfunction "1_1") (pintype "passive"))
      (node (ref "RN1") (pin "6") (pinfunction "1_6") (pintype "passive"))
      (node (ref "RN2") (pin "4") (pinfunction "4_4") (pintype "passive"))
    )
    (net (code "125") (name "Net-(RN1G-1)") (class "Default")
      (node (ref "JP14") (pin "9") (pinfunction "9_9") (pintype "passive"))
      (node (ref "JP2") (pin "7") (pinfunction "7_7") (pintype "passive"))
      (node (ref "R29") (pin "2") (pinfunction "2_2") (pintype "passive"))
      (node (ref "R51") (pin "1") (pinfunction "1_1") (pintype "passive"))
      (node (ref "RN1") (pin "7") (pinfunction "1_7") (pintype "passive"))
      (node (ref "RN2") (pin "3") (pinfunction "3_3") (pintype "passive"))
    )
    (net (code "126") (name "Net-(RN1H-1)") (class "Default")
      (node (ref "JP14") (pin "10") (pinfunction "10_10") (pintype "passive"))
      (node (ref "JP2") (pin "8") (pinfunction "8_8") (pintype "passive"))
      (node (ref "R28") (pin "2") (pinfunction "2_2") (pintype "passive"))
      (node (ref "R52") (pin "1") (pinfunction "1_1") (pintype "passive"))
      (node (ref "RN1") (pin "8") (pinfunction "1_8") (pintype "passive"))
      (node (ref "RN2") (pin "2") (pinfunction "2_2") (pintype "passive"))
    )
    (net (code "127") (name "Net-(RN4B-1)") (class "Default")
      (node (ref "JP13") (pin "2") (pinfunction "2_2") (pintype "passive"))
      (node (ref "JP3") (pin "2") (pinfunction "2_2") (pintype "passive"))
      (node (ref "R43") (pin "2") (pinfunction "2_2") (pintype "passive"))
      (node (ref "R54") (pin "2") (pinfunction "2_2") (pintype "passive"))
      (node (ref "RN4") (pin "2") (pinfunction "1_2") (pintype "passive"))
      (node (ref "RN5") (pin "8") (pinfunction "8_8") (pintype "passive"))
    )
    (net (code "128") (name "Net-(RN4C-1)") (class "Default")
      (node (ref "JP13") (pin "3") (pinfunction "3_3") (pintype "passive"))
      (node (ref "JP3") (pin "3") (pinfunction "3_3") (pintype "passive"))
      (node (ref "R42") (pin "2") (pinfunction "2_2") (pintype "passive"))
      (node (ref "R55") (pin "2") (pinfunction "2_2") (pintype "passive"))
      (node (ref "RN4") (pin "3") (pinfunction "1_3") (pintype "passive"))
      (node (ref "RN5") (pin "7") (pinfunction "7_7") (pintype "passive"))
    )
    (net (code "129") (name "Net-(RN4D-1)") (class "Default")
      (node (ref "JP13") (pin "4") (pinfunction "4_4") (pintype "passive"))
      (node (ref "JP3") (pin "4") (pinfunction "4_4") (pintype "passive"))
      (node (ref "R41") (pin "2") (pinfunction "2_2") (pintype "passive"))
      (node (ref "R56") (pin "2") (pinfunction "2_2") (pintype "passive"))
      (node (ref "RN4") (pin "4") (pinfunction "1_4") (pintype "passive"))
      (node (ref "RN5") (pin "6") (pinfunction "6_6") (pintype "passive"))
    )
    (net (code "130") (name "Net-(RN4E-1)") (class "Default")
      (node (ref "JP13") (pin "7") (pinfunction "7_7") (pintype "passive"))
      (node (ref "JP3") (pin "5") (pinfunction "5_5") (pintype "passive"))
      (node (ref "R39") (pin "2") (pinfunction "2_2") (pintype "passive"))
      (node (ref "R57") (pin "2") (pinfunction "2_2") (pintype "passive"))
      (node (ref "RN4") (pin "5") (pinfunction "1_5") (pintype "passive"))
      (node (ref "RN5") (pin "5") (pinfunction "5_5") (pintype "passive"))
    )
    (net (code "131") (name "Net-(RN4F-1)") (class "Default")
      (node (ref "JP13") (pin "8") (pinfunction "8_8") (pintype "passive"))
      (node (ref "JP3") (pin "6") (pinfunction "6_6") (pintype "passive"))
      (node (ref "R38") (pin "2") (pinfunction "2_2") (pintype "passive"))
      (node (ref "R58") (pin "2") (pinfunction "2_2") (pintype "passive"))
      (node (ref "RN4") (pin "6") (pinfunction "1_6") (pintype "passive"))
      (node (ref "RN5") (pin "4") (pinfunction "4_4") (pintype "passive"))
    )
    (net (code "132") (name "Net-(RN4G-1)") (class "Default")
      (node (ref "JP13") (pin "9") (pinfunction "9_9") (pintype "passive"))
      (node (ref "JP3") (pin "7") (pinfunction "7_7") (pintype "passive"))
      (node (ref "R37") (pin "2") (pinfunction "2_2") (pintype "passive"))
      (node (ref "R59") (pin "2") (pinfunction "2_2") (pintype "passive"))
      (node (ref "RN4") (pin "7") (pinfunction "1_7") (pintype "passive"))
      (node (ref "RN5") (pin "3") (pinfunction "3_3") (pintype "passive"))
    )
    (net (code "133") (name "Net-(RN4H-1)") (class "Default")
      (node (ref "JP13") (pin "10") (pinfunction "10_10") (pintype "passive"))
      (node (ref "JP3") (pin "8") (pinfunction "8_8") (pintype "passive"))
      (node (ref "R36") (pin "2") (pinfunction "2_2") (pintype "passive"))
      (node (ref "R60") (pin "2") (pinfunction "2_2") (pintype "passive"))
      (node (ref "RN4") (pin "8") (pinfunction "1_8") (pintype "passive"))
      (node (ref "RN5") (pin "2") (pinfunction "2_2") (pintype "passive"))
    )
    (net (code "134") (name "Net-(SJ13-Pad1)") (class "Default")
      (node (ref "SJ13") (pin "1") (pinfunction "1_1") (pintype "passive"))
      (node (ref "U$1") (pin "PB14") (pinfunction "PB14_PB14") (pintype "bidirectional"))
    )
    (net (code "135") (name "Net-(SJ14-1)") (class "Default")
      (node (ref "SJ14") (pin "P$1") (pinfunction "1_P$1") (pintype "passive"))
      (node (ref "U$1") (pin "VIN2") (pinfunction "VIN2_VIN2") (pintype "power_in"))
    )
    (net (code "136") (name "Net-(SJ16-2)") (class "Default")
      (node (ref "JP9") (pin "2") (pinfunction "2_2") (pintype "passive"))
      (node (ref "SJ15") (pin "2") (pinfunction "2_2") (pintype "passive"))
      (node (ref "SJ16") (pin "P$2") (pinfunction "2_P$2") (pintype "passive"))
    )
    (net (code "137") (name "OLAT") (class "Default")
      (node (ref "IC3") (pin "12") (pinfunction "RCK_12") (pintype "input"))
      (node (ref "IC5") (pin "12") (pinfunction "RCK_12") (pintype "input"))
      (node (ref "R21") (pin "1") (pinfunction "1_1") (pintype "passive"))
      (node (ref "U$1") (pin "PA8") (pinfunction "PA8_PA8") (pintype "bidirectional"))
    )
    (net (code "138") (name "SCK") (class "Default")
      (node (ref "IC3") (pin "11") (pinfunction "SCK_11") (pintype "input"))
      (node (ref "IC5") (pin "11") (pinfunction "SCK_11") (pintype "input"))
      (node (ref "JP9") (pin "3") (pinfunction "3_3") (pintype "passive"))
      (node (ref "R19") (pin "1") (pinfunction "1_1") (pintype "passive"))
      (node (ref "U$1") (pin "PB3") (pinfunction "PB3_PB3") (pintype "bidirectional"))
    )
    (net (code "139") (name "SCK2") (class "Default")
      (node (ref "IC1") (pin "7") (pinfunction "CLK_7") (pintype "input"))
      (node (ref "IC4") (pin "7") (pinfunction "CLK_7") (pintype "input"))
      (node (ref "U$1") (pin "PB10") (pinfunction "PB10_PB10") (pintype "bidirectional"))
    )
    (net (code "140") (name "SLNK1") (class "Default")
      (node (ref "IC3") (pin "14") (pinfunction "SER_14") (pintype "input"))
      (node (ref "IC5") (pin "9") (pinfunction "QH*_9") (pintype "tri_state"))
      (node (ref "SJ17") (pin "P$1") (pinfunction "1_P$1") (pintype "passive"))
    )
    (net (code "141") (name "SLNK2") (class "Default")
      (node (ref "IC3") (pin "9") (pinfunction "QH*_9") (pintype "tri_state"))
      (node (ref "SJ16") (pin "P$1") (pinfunction "1_P$1") (pintype "passive"))
    )
    (net (code "142") (name "SLNK3") (class "Default")
      (node (ref "IC1") (pin "13") (pinfunction "QH_13") (pintype "output"))
      (node (ref "IC4") (pin "1") (pinfunction "SER_1") (pintype "input"))
    )
    (net (code "143") (name "SRV1") (class "Default")
      (node (ref "JP7") (pin "2") (pinfunction "2_2") (pintype "passive"))
      (node (ref "R25") (pin "2") (pinfunction "2_2") (pintype "passive"))
      (node (ref "U$1") (pin "PC9") (pinfunction "PC9_PC9") (pintype "bidirectional"))
    )
    (net (code "144") (name "SRV2") (class "Default")
      (node (ref "JP7") (pin "1") (pinfunction "1_1") (pintype "passive"))
      (node (ref "R24") (pin "2") (pinfunction "2_2") (pintype "passive"))
      (node (ref "U$1") (pin "PC7") (pinfunction "PC7_PC7") (pintype "bidirectional"))
    )
    (net (code "145") (name "SRV3") (class "Default")
      (node (ref "JP11") (pin "2") (pinfunction "2_2") (pintype "passive"))
      (node (ref "R26") (pin "2") (pinfunction "2_2") (pintype "passive"))
      (node (ref "U$1") (pin "PC8") (pinfunction "PC8_PC8") (pintype "bidirectional"))
    )
    (net (code "146") (name "SRV4") (class "Default")
      (node (ref "JP11") (pin "1") (pinfunction "1_1") (pintype "passive"))
      (node (ref "R27") (pin "2") (pinfunction "2_2") (pintype "passive"))
      (node (ref "U$1") (pin "PC6") (pinfunction "PC6_PC6") (pintype "bidirectional"))
    )
    (net (code "147") (name "TIN3") (class "Default")
      (node (ref "IC9") (pin "10") (pinfunction "+IN_10") (pintype "input"))
      (node (ref "U$1") (pin "PB15") (pinfunction "PB15_PB15") (pintype "bidirectional"))
      (node (ref "U$2") (pin "4") (pinfunction "I_4") (pintype "input"))
    )
    (net (code "148") (name "TIN4") (class "Default")
      (node (ref "IC9") (pin "12") (pinfunction "+IN_12") (pintype "input"))
      (node (ref "U$1") (pin "PB12") (pinfunction "PB12_PB12") (pintype "bidirectional"))
      (node (ref "U$3") (pin "2") (pinfunction "I_2") (pintype "input"))
    )
    (net (code "149") (name "V+") (class "Default")
      (node (ref "AP1509") (pin "3") (pinfunction "FB_3") (pintype "bidirectional"))
      (node (ref "C1") (pin "1") (pinfunction "1_1") (pintype "passive"))
      (node (ref "C2") (pin "+") (pinfunction "+_+") (pintype "passive"))
      (node (ref "IC10") (pin "1") (pinfunction "FB_1") (pintype "input"))
      (node (ref "L1") (pin "1") (pinfunction "1_1") (pintype "passive"))
      (node (ref "U$1") (pin "E5V") (pinfunction "E5V_E5V") (pintype "power_in"))
    )
    (net (code "150") (name "unconnected-(H1-MOUNT-PadB3,3)") (class "Default")
      (node (ref "H1") (pin "B3,3") (pinfunction "MOUNT_B3,3") (pintype "passive"))
    )
    (net (code "151") (name "unconnected-(H2-MOUNT-PadB3,3)") (class "Default")
      (node (ref "H2") (pin "B3,3") (pinfunction "MOUNT_B3,3") (pintype "passive"))
    )
    (net (code "152") (name "unconnected-(H3-MOUNT-PadB3,3)") (class "Default")
      (node (ref "H3") (pin "B3,3") (pinfunction "MOUNT_B3,3") (pintype "passive"))
    )
    (net (code "153") (name "unconnected-(H4-MOUNT-PadB3,3)") (class "Default")
      (node (ref "H4") (pin "B3,3") (pinfunction "MOUNT_B3,3") (pintype "passive"))
    )
    (net (code "154") (name "unconnected-(J3-Pad2)") (class "Default")
      (node (ref "J3") (pin "2") (pinfunction "2_2") (pintype "passive"))
    )
    (net (code "155") (name "unconnected-(U$1-PadBOOT0)") (class "Default")
      (node (ref "U$1") (pin "BOOT0") (pinfunction "BOOT0_BOOT0") (pintype "bidirectional"))
    )
    (net (code "156") (name "unconnected-(U$1-PadIOREF2)") (class "Default")
      (node (ref "U$1") (pin "IOREF2") (pinfunction "IOREF2_IOREF2") (pintype "input"))
    )
    (net (code "157") (name "unconnected-(U$1-PadNC1-PF7)") (class "Default")
      (node (ref "U$1") (pin "NC1-PF7") (pinfunction "NC1-PF7_NC1-PF7") (pintype "bidirectional"))
    )
    (net (code "158") (name "unconnected-(U$1-PadNC2-PF6)") (class "Default")
      (node (ref "U$1") (pin "NC2-PF6") (pinfunction "NC2-PF6_NC2-PF6") (pintype "bidirectional"))
    )
    (net (code "159") (name "unconnected-(U$1-PadNC3)") (class "Default")
      (node (ref "U$1") (pin "NC3") (pinfunction "NC3_NC3") (pintype "no_connect"))
    )
    (net (code "160") (name "unconnected-(U$1-PadNC4)") (class "Default")
      (node (ref "U$1") (pin "NC4") (pinfunction "NC4_NC4") (pintype "no_connect"))
    )
    (net (code "161") (name "unconnected-(U$1-PadNC5-PD8)") (class "Default")
      (node (ref "U$1") (pin "NC5-PD8") (pinfunction "NC5-PD8_NC5-PD8") (pintype "bidirectional"))
    )
    (net (code "162") (name "unconnected-(U$1-PadNC6-PB11)") (class "Default")
      (node (ref "U$1") (pin "NC6-PB11") (pinfunction "NC6-PB11_NC6-PB11") (pintype "no_connect"))
    )
    (net (code "163") (name "unconnected-(U$1-PadNC7-PF5)") (class "Default")
      (node (ref "U$1") (pin "NC7-PF5") (pinfunction "NC7-PF5_NC7-PF5") (pintype "bidirectional"))
    )
    (net (code "164") (name "unconnected-(U$1-PadNC8-PF4)") (class "Default")
      (node (ref "U$1") (pin "NC8-PF4") (pinfunction "NC8-PF4_NC8-PF4") (pintype "bidirectional"))
    )
    (net (code "165") (name "unconnected-(U$1-PadNRESET)") (class "Default")
      (node (ref "U$1") (pin "NRESET") (pinfunction "NRESET_NRESET") (pintype "input"))
    )
    (net (code "166") (name "unconnected-(U$1-PadPA1)") (class "Default")
      (node (ref "U$1") (pin "PA1") (pinfunction "PA1_PA1") (pintype "bidirectional"))
    )
    (net (code "167") (name "unconnected-(U$1-PadPA2)") (class "Default")
      (node (ref "U$1") (pin "PA2") (pinfunction "PA2_PA2") (pintype "bidirectional"))
    )
    (net (code "168") (name "unconnected-(U$1-PadPA3)") (class "Default")
      (node (ref "U$1") (pin "PA3") (pinfunction "PA3_PA3") (pintype "bidirectional"))
    )
    (net (code "169") (name "unconnected-(U$1-PadPA5)") (class "Default")
      (node (ref "U$1") (pin "PA5") (pinfunction "PA5_PA5") (pintype "bidirectional"))
    )
    (net (code "170") (name "unconnected-(U$1-PadPA7)") (class "Default")
      (node (ref "U$1") (pin "PA7") (pinfunction "PA7_PA7") (pintype "bidirectional"))
    )
    (net (code "171") (name "unconnected-(U$1-PadPA9)") (class "Default")
      (node (ref "U$1") (pin "PA9") (pinfunction "PA9_PA9") (pintype "bidirectional"))
    )
    (net (code "172") (name "unconnected-(U$1-PadPA10)") (class "Default")
      (node (ref "U$1") (pin "PA10") (pinfunction "PA10_PA10") (pintype "bidirectional"))
    )
    (net (code "173") (name "unconnected-(U$1-PadPA11)") (class "Default")
      (node (ref "U$1") (pin "PA11") (pinfunction "PA11_PA11") (pintype "bidirectional"))
    )
    (net (code "174") (name "unconnected-(U$1-PadPA12)") (class "Default")
      (node (ref "U$1") (pin "PA12") (pinfunction "PA12_PA12") (pintype "bidirectional"))
    )
    (net (code "175") (name "unconnected-(U$1-PadPA13)") (class "Default")
      (node (ref "U$1") (pin "PA13") (pinfunction "PA13_PA13") (pintype "bidirectional"))
    )
    (net (code "176") (name "unconnected-(U$1-PadPA14)") (class "Default")
      (node (ref "U$1") (pin "PA14") (pinfunction "PA14_PA14") (pintype "bidirectional"))
    )
    (net (code "177") (name "unconnected-(U$1-PadPB0)") (class "Default")
      (node (ref "U$1") (pin "PB0") (pinfunction "PB0_PB0") (pintype "bidirectional"))
    )
    (net (code "178") (name "unconnected-(U$1-PadPB13)") (class "Default")
      (node (ref "U$1") (pin "PB13") (pinfunction "PB13_PB13") (pintype "bidirectional"))
    )
    (net (code "179") (name "unconnected-(U$1-PadPC1)") (class "Default")
      (node (ref "U$1") (pin "PC1") (pinfunction "PC1_PC1") (pintype "bidirectional"))
    )
    (net (code "180") (name "unconnected-(U$1-PadPC4)") (class "Default")
      (node (ref "U$1") (pin "PC4") (pinfunction "PC4_PC4") (pintype "bidirectional"))
    )
    (net (code "181") (name "unconnected-(U$1-PadPC5)") (class "Default")
      (node (ref "U$1") (pin "PC5") (pinfunction "PC5_PC5") (pintype "bidirectional"))
    )
    (net (code "182") (name "unconnected-(U$1-PadPC13)") (class "Default")
      (node (ref "U$1") (pin "PC13") (pinfunction "PC13_PC13") (pintype "bidirectional"))
    )
    (net (code "183") (name "unconnected-(U$1-PadPC14)") (class "Default")
      (node (ref "U$1") (pin "PC14") (pinfunction "PC14_PC14") (pintype "bidirectional"))
    )
    (net (code "184") (name "unconnected-(U$1-PadPC15)") (class "Default")
      (node (ref "U$1") (pin "PC15") (pinfunction "PC15_PC15") (pintype "bidirectional"))
    )
    (net (code "185") (name "unconnected-(U$1-PadPF0-PH0)") (class "Default")
      (node (ref "U$1") (pin "PF0-PH0") (pinfunction "PF0-PH0_PF0-PH0") (pintype "bidirectional"))
    )
  )
)
